# USB3-PCIEv21.net
KiCad netlist of a schematic drawn in Altium Designer
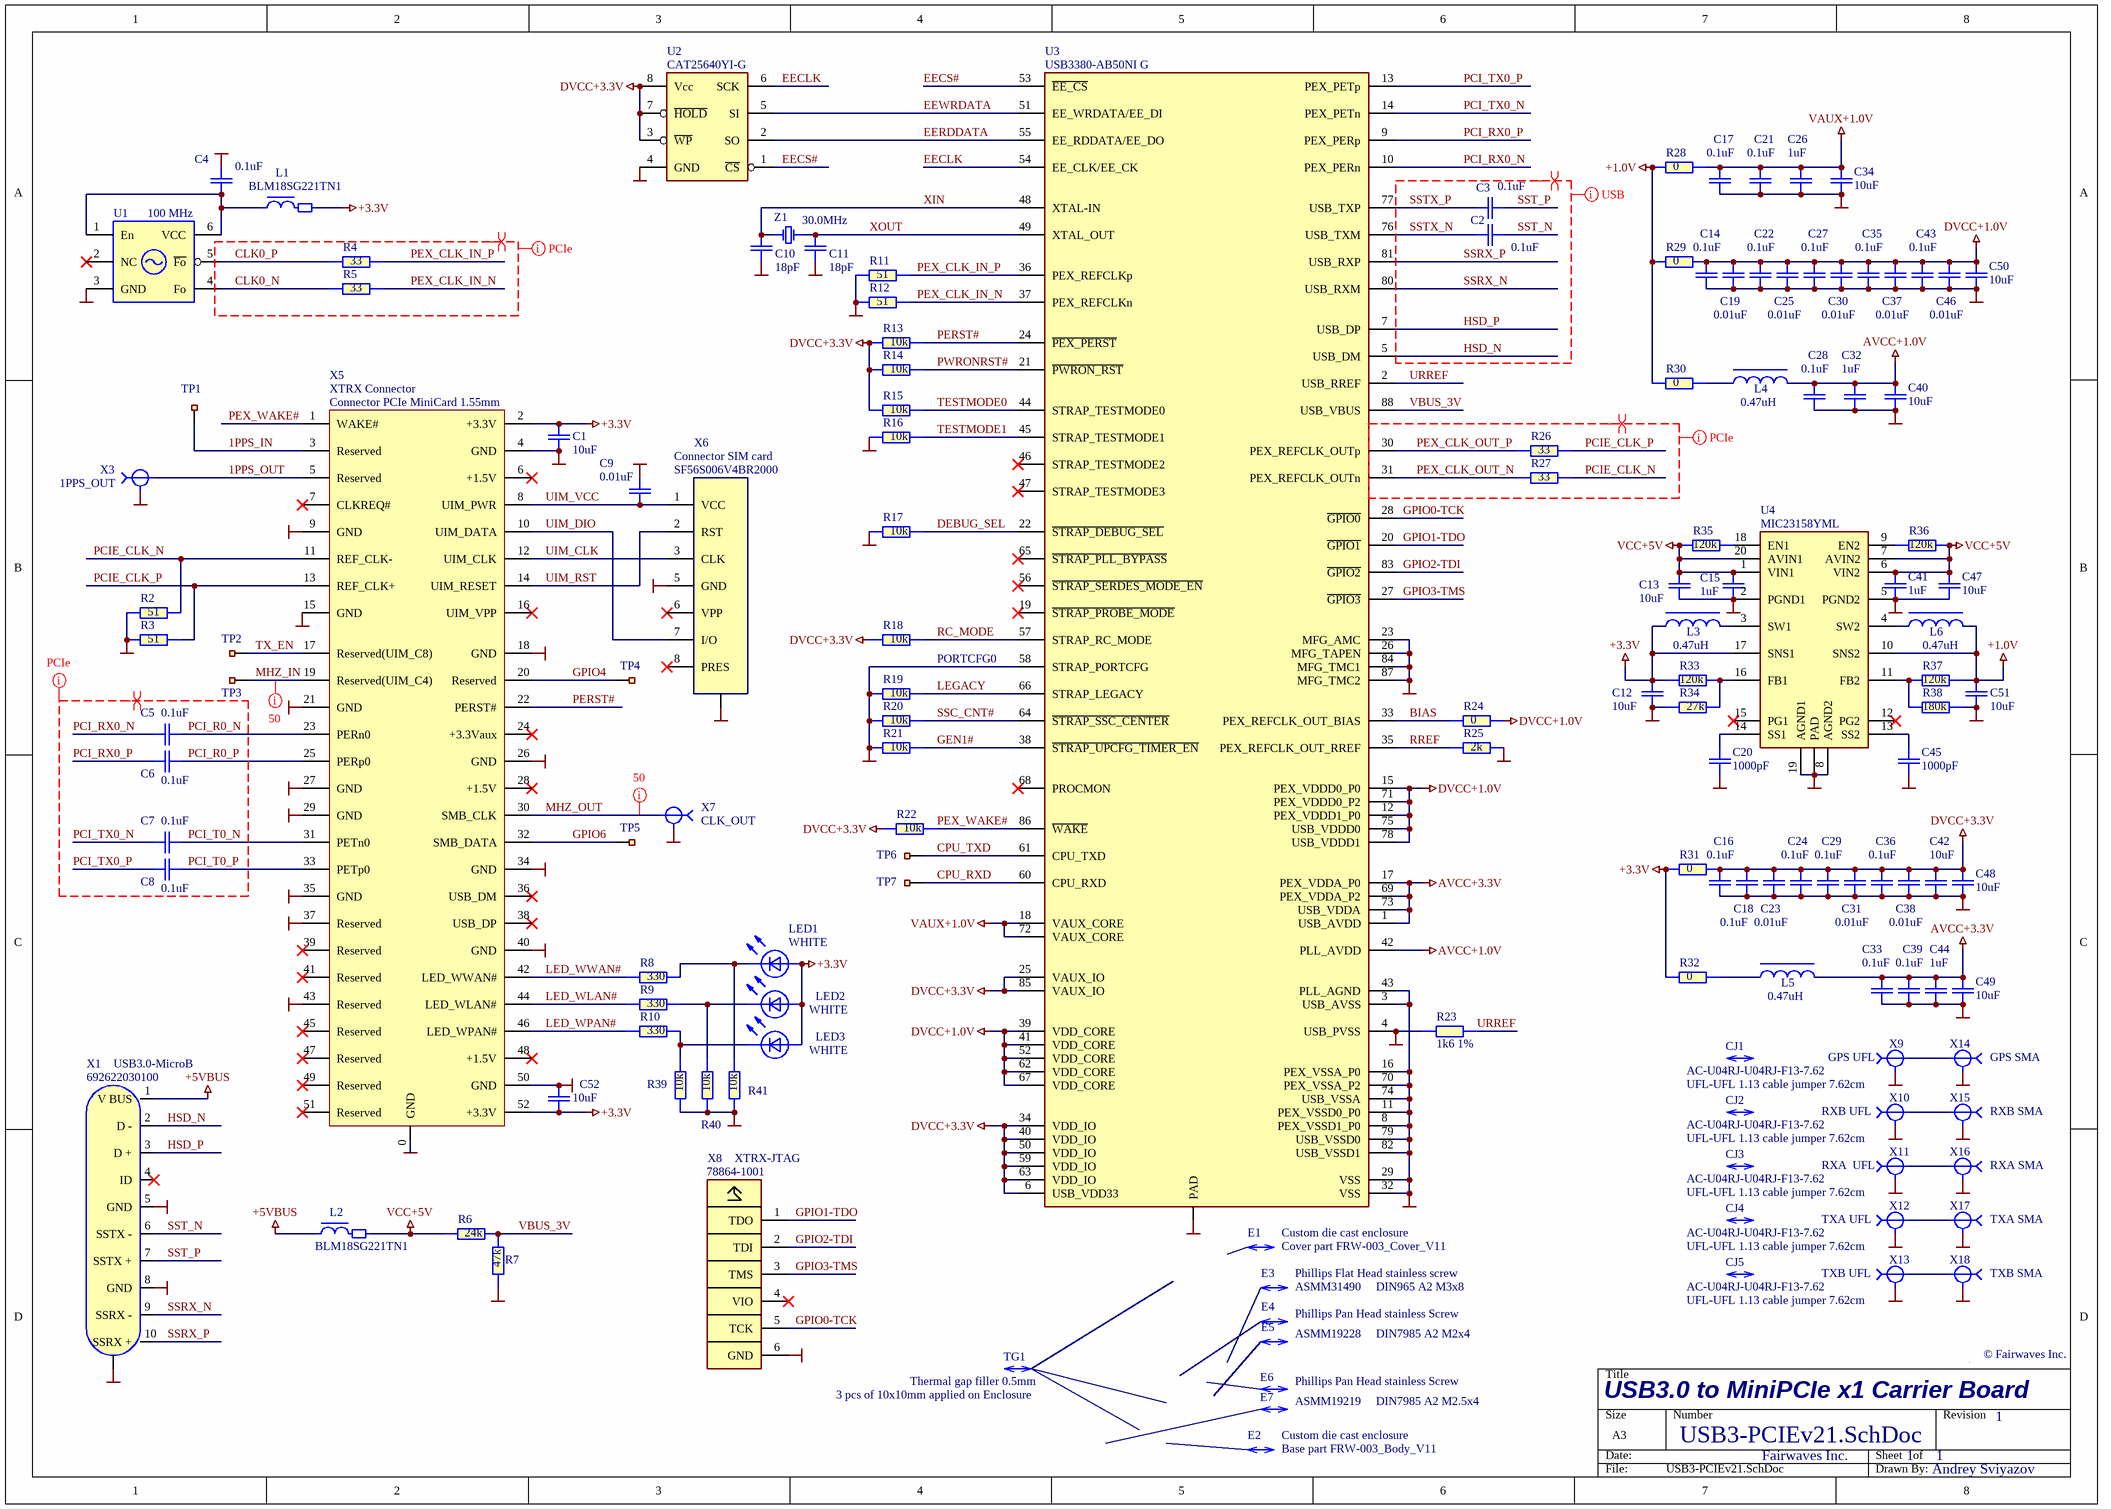
[diagram p0: USB3-PCIEv21.SchDoc]

(export (version "E")
  (design (tool "Eeschema 10.0.6"))
  (components
    (comp (ref "C1")
      (value "10uF")
      (footprint "C0402-Phillips")
      (description "Capacitor")
      (fields (field (name "MANUFACTURER") "MuRata") (field (name "TOLERANCE") "20%"))
      (libsource (lib "Capacitors") (part "C0402"))
    )
    (comp (ref "C2")
      (value "0.1uF")
      (footprint "C0402-Phillips")
      (description "Capacitor")
      (fields (field (name "MANUFACTURER") "YAGEO") (field (name "TOLERANCE") "20%"))
      (libsource (lib "Capacitors") (part "C0402"))
    )
    (comp (ref "C3")
      (value "0.1uF")
      (footprint "C0402-Phillips")
      (description "Capacitor")
      (fields (field (name "MANUFACTURER") "YAGEO") (field (name "TOLERANCE") "20%"))
      (libsource (lib "Capacitors") (part "C0402"))
    )
    (comp (ref "C4")
      (value "0.1uF")
      (footprint "C0402-Phillips")
      (description "Capacitor")
      (fields (field (name "MANUFACTURER") "YAGEO") (field (name "TOLERANCE") "20%"))
      (libsource (lib "Capacitors") (part "C0402"))
    )
    (comp (ref "C5")
      (value "0.1uF")
      (footprint "C0402-Phillips")
      (description "Capacitor")
      (fields (field (name "MANUFACTURER") "YAGEO") (field (name "TOLERANCE") "20%"))
      (libsource (lib "Capacitors") (part "C0402"))
    )
    (comp (ref "C6")
      (value "0.1uF")
      (footprint "C0402-Phillips")
      (description "Capacitor")
      (fields (field (name "MANUFACTURER") "YAGEO") (field (name "TOLERANCE") "20%"))
      (libsource (lib "Capacitors") (part "C0402"))
    )
    (comp (ref "C7")
      (value "0.1uF")
      (footprint "C0402-Phillips")
      (description "Capacitor")
      (fields (field (name "MANUFACTURER") "YAGEO") (field (name "TOLERANCE") "20%"))
      (libsource (lib "Capacitors") (part "C0402"))
    )
    (comp (ref "C8")
      (value "0.1uF")
      (footprint "C0402-Phillips")
      (description "Capacitor")
      (fields (field (name "MANUFACTURER") "YAGEO") (field (name "TOLERANCE") "20%"))
      (libsource (lib "Capacitors") (part "C0402"))
    )
    (comp (ref "C9")
      (value "0.01uF")
      (footprint "C0402-Phillips")
      (description "Capacitor")
      (fields (field (name "MANUFACTURER") "YAGEO") (field (name "TOLERANCE") "20%"))
      (libsource (lib "Capacitors") (part "C0402"))
    )
    (comp (ref "C10")
      (value "18pF")
      (footprint "C0402-Phillips")
      (description "Capacitor")
      (fields (field (name "MANUFACTURER") "Yageo") (field (name "TOLERANCE") "10%"))
      (libsource (lib "Capacitors") (part "C0402"))
    )
    (comp (ref "C11")
      (value "18pF")
      (footprint "C0402-Phillips")
      (description "Capacitor")
      (fields (field (name "MANUFACTURER") "Yageo") (field (name "TOLERANCE") "10%"))
      (libsource (lib "Capacitors") (part "C0402"))
    )
    (comp (ref "C12")
      (value "10uF")
      (footprint "C0402-Phillips")
      (description "Capacitor")
      (fields (field (name "MANUFACTURER") "MuRata") (field (name "TOLERANCE") "20%"))
      (libsource (lib "Capacitors") (part "C0402"))
    )
    (comp (ref "C13")
      (value "10uF")
      (footprint "C0402-Phillips")
      (description "Capacitor")
      (fields (field (name "MANUFACTURER") "MuRata") (field (name "TOLERANCE") "20%"))
      (libsource (lib "Capacitors") (part "C0402"))
    )
    (comp (ref "C14")
      (value "0.1uF")
      (footprint "C0402-Phillips")
      (description "Capacitor")
      (fields (field (name "MANUFACTURER") "YAGEO") (field (name "TOLERANCE") "20%"))
      (libsource (lib "Capacitors") (part "C0402"))
    )
    (comp (ref "C15")
      (value "1uF")
      (footprint "C0402-Phillips")
      (description "Capacitor")
      (fields (field (name "MANUFACTURER") "MuRata") (field (name "TOLERANCE") "20%"))
      (libsource (lib "Capacitors") (part "C0402"))
    )
    (comp (ref "C16")
      (value "0.1uF")
      (footprint "C0402-Phillips")
      (description "Capacitor")
      (fields (field (name "MANUFACTURER") "YAGEO") (field (name "TOLERANCE") "20%"))
      (libsource (lib "Capacitors") (part "C0402"))
    )
    (comp (ref "C17")
      (value "0.1uF")
      (footprint "C0402-Phillips")
      (description "Capacitor")
      (fields (field (name "MANUFACTURER") "YAGEO") (field (name "TOLERANCE") "20%"))
      (libsource (lib "Capacitors") (part "C0402"))
    )
    (comp (ref "C18")
      (value "0.1uF")
      (footprint "C0402-Phillips")
      (description "Capacitor")
      (fields (field (name "MANUFACTURER") "YAGEO") (field (name "TOLERANCE") "20%"))
      (libsource (lib "Capacitors") (part "C0402"))
    )
    (comp (ref "C19")
      (value "0.01uF")
      (footprint "C0402-Phillips")
      (description "Capacitor")
      (fields (field (name "MANUFACTURER") "YAGEO") (field (name "TOLERANCE") "20%"))
      (libsource (lib "Capacitors") (part "C0402"))
    )
    (comp (ref "C20")
      (value "1000pF")
      (footprint "C0402-Phillips")
      (description "Capacitor")
      (fields (field (name "MANUFACTURER") "MuRata") (field (name "TOLERANCE") "20%"))
      (libsource (lib "Capacitors") (part "C0402"))
    )
    (comp (ref "C21")
      (value "0.1uF")
      (footprint "C0402-Phillips")
      (description "Capacitor")
      (fields (field (name "MANUFACTURER") "YAGEO") (field (name "TOLERANCE") "20%"))
      (libsource (lib "Capacitors") (part "C0402"))
    )
    (comp (ref "C22")
      (value "0.1uF")
      (footprint "C0402-Phillips")
      (description "Capacitor")
      (fields (field (name "MANUFACTURER") "YAGEO") (field (name "TOLERANCE") "20%"))
      (libsource (lib "Capacitors") (part "C0402"))
    )
    (comp (ref "C23")
      (value "0.01uF")
      (footprint "C0402-Phillips")
      (description "Capacitor")
      (fields (field (name "MANUFACTURER") "YAGEO") (field (name "TOLERANCE") "20%"))
      (libsource (lib "Capacitors") (part "C0402"))
    )
    (comp (ref "C24")
      (value "0.1uF")
      (footprint "C0402-Phillips")
      (description "Capacitor")
      (fields (field (name "MANUFACTURER") "YAGEO") (field (name "TOLERANCE") "20%"))
      (libsource (lib "Capacitors") (part "C0402"))
    )
    (comp (ref "C25")
      (value "0.01uF")
      (footprint "C0402-Phillips")
      (description "Capacitor")
      (fields (field (name "MANUFACTURER") "YAGEO") (field (name "TOLERANCE") "20%"))
      (libsource (lib "Capacitors") (part "C0402"))
    )
    (comp (ref "C26")
      (value "1uF")
      (footprint "C0402-Phillips")
      (description "Capacitor")
      (fields (field (name "MANUFACTURER") "MuRata") (field (name "TOLERANCE") "20%"))
      (libsource (lib "Capacitors") (part "C0402"))
    )
    (comp (ref "C27")
      (value "0.1uF")
      (footprint "C0402-Phillips")
      (description "Capacitor")
      (fields (field (name "MANUFACTURER") "YAGEO") (field (name "TOLERANCE") "20%"))
      (libsource (lib "Capacitors") (part "C0402"))
    )
    (comp (ref "C28")
      (value "0.1uF")
      (footprint "C0402-Phillips")
      (description "Capacitor")
      (fields (field (name "MANUFACTURER") "YAGEO") (field (name "TOLERANCE") "20%"))
      (libsource (lib "Capacitors") (part "C0402"))
    )
    (comp (ref "C29")
      (value "0.1uF")
      (footprint "C0402-Phillips")
      (description "Capacitor")
      (fields (field (name "MANUFACTURER") "YAGEO") (field (name "TOLERANCE") "20%"))
      (libsource (lib "Capacitors") (part "C0402"))
    )
    (comp (ref "C30")
      (value "0.01uF")
      (footprint "C0402-Phillips")
      (description "Capacitor")
      (fields (field (name "MANUFACTURER") "YAGEO") (field (name "TOLERANCE") "20%"))
      (libsource (lib "Capacitors") (part "C0402"))
    )
    (comp (ref "C31")
      (value "0.01uF")
      (footprint "C0402-Phillips")
      (description "Capacitor")
      (fields (field (name "MANUFACTURER") "YAGEO") (field (name "TOLERANCE") "20%"))
      (libsource (lib "Capacitors") (part "C0402"))
    )
    (comp (ref "C32")
      (value "1uF")
      (footprint "C0402-Phillips")
      (description "Capacitor")
      (fields (field (name "MANUFACTURER") "MuRata") (field (name "TOLERANCE") "20%"))
      (libsource (lib "Capacitors") (part "C0402"))
    )
    (comp (ref "C33")
      (value "0.1uF")
      (footprint "C0402-Phillips")
      (description "Capacitor")
      (fields (field (name "MANUFACTURER") "YAGEO") (field (name "TOLERANCE") "20%"))
      (libsource (lib "Capacitors") (part "C0402"))
    )
    (comp (ref "C34")
      (value "10uF")
      (footprint "C0402-Phillips")
      (description "Capacitor")
      (fields (field (name "MANUFACTURER") "MuRata") (field (name "TOLERANCE") "20%"))
      (libsource (lib "Capacitors") (part "C0402"))
    )
    (comp (ref "C35")
      (value "0.1uF")
      (footprint "C0402-Phillips")
      (description "Capacitor")
      (fields (field (name "MANUFACTURER") "YAGEO") (field (name "TOLERANCE") "20%"))
      (libsource (lib "Capacitors") (part "C0402"))
    )
    (comp (ref "C36")
      (value "0.1uF")
      (footprint "C0402-Phillips")
      (description "Capacitor")
      (fields (field (name "MANUFACTURER") "YAGEO") (field (name "TOLERANCE") "20%"))
      (libsource (lib "Capacitors") (part "C0402"))
    )
    (comp (ref "C37")
      (value "0.01uF")
      (footprint "C0402-Phillips")
      (description "Capacitor")
      (fields (field (name "MANUFACTURER") "YAGEO") (field (name "TOLERANCE") "20%"))
      (libsource (lib "Capacitors") (part "C0402"))
    )
    (comp (ref "C38")
      (value "0.01uF")
      (footprint "C0402-Phillips")
      (description "Capacitor")
      (fields (field (name "MANUFACTURER") "YAGEO") (field (name "TOLERANCE") "20%"))
      (libsource (lib "Capacitors") (part "C0402"))
    )
    (comp (ref "C39")
      (value "0.1uF")
      (footprint "C0402-Phillips")
      (description "Capacitor")
      (fields (field (name "MANUFACTURER") "YAGEO") (field (name "TOLERANCE") "20%"))
      (libsource (lib "Capacitors") (part "C0402"))
    )
    (comp (ref "C40")
      (value "10uF")
      (footprint "C0402-Phillips")
      (description "Capacitor")
      (fields (field (name "MANUFACTURER") "MuRata") (field (name "TOLERANCE") "20%"))
      (libsource (lib "Capacitors") (part "C0402"))
    )
    (comp (ref "C41")
      (value "1uF")
      (footprint "C0402-Phillips")
      (description "Capacitor")
      (fields (field (name "MANUFACTURER") "MuRata") (field (name "TOLERANCE") "20%"))
      (libsource (lib "Capacitors") (part "C0402"))
    )
    (comp (ref "C42")
      (value "10uF")
      (footprint "C0402-Phillips")
      (description "Capacitor")
      (fields (field (name "MANUFACTURER") "MuRata") (field (name "TOLERANCE") "20%"))
      (libsource (lib "Capacitors") (part "C0402"))
    )
    (comp (ref "C43")
      (value "0.1uF")
      (footprint "C0402-Phillips")
      (description "Capacitor")
      (fields (field (name "MANUFACTURER") "YAGEO") (field (name "TOLERANCE") "20%"))
      (libsource (lib "Capacitors") (part "C0402"))
    )
    (comp (ref "C44")
      (value "1uF")
      (footprint "C0402-Phillips")
      (description "Capacitor")
      (fields (field (name "MANUFACTURER") "MuRata") (field (name "TOLERANCE") "20%"))
      (libsource (lib "Capacitors") (part "C0402"))
    )
    (comp (ref "C45")
      (value "1000pF")
      (footprint "C0402-Phillips")
      (description "Capacitor")
      (fields (field (name "MANUFACTURER") "MuRata") (field (name "TOLERANCE") "20%"))
      (libsource (lib "Capacitors") (part "C0402"))
    )
    (comp (ref "C46")
      (value "0.01uF")
      (footprint "C0402-Phillips")
      (description "Capacitor")
      (fields (field (name "MANUFACTURER") "YAGEO") (field (name "TOLERANCE") "20%"))
      (libsource (lib "Capacitors") (part "C0402"))
    )
    (comp (ref "C47")
      (value "10uF")
      (footprint "C0402-Phillips")
      (description "Capacitor")
      (fields (field (name "MANUFACTURER") "MuRata") (field (name "TOLERANCE") "20%"))
      (libsource (lib "Capacitors") (part "C0402"))
    )
    (comp (ref "C48")
      (value "10uF")
      (footprint "C0402-Phillips")
      (description "Capacitor")
      (fields (field (name "MANUFACTURER") "MuRata") (field (name "TOLERANCE") "20%"))
      (libsource (lib "Capacitors") (part "C0402"))
    )
    (comp (ref "C49")
      (value "10uF")
      (footprint "C0402-Phillips")
      (description "Capacitor")
      (fields (field (name "MANUFACTURER") "MuRata") (field (name "TOLERANCE") "20%"))
      (libsource (lib "Capacitors") (part "C0402"))
    )
    (comp (ref "C50")
      (value "10uF")
      (footprint "C0402-Phillips")
      (description "Capacitor")
      (fields (field (name "MANUFACTURER") "MuRata") (field (name "TOLERANCE") "20%"))
      (libsource (lib "Capacitors") (part "C0402"))
    )
    (comp (ref "C51")
      (value "10uF")
      (footprint "C0402-Phillips")
      (description "Capacitor")
      (fields (field (name "MANUFACTURER") "MuRata") (field (name "TOLERANCE") "20%"))
      (libsource (lib "Capacitors") (part "C0402"))
    )
    (comp (ref "C52")
      (value "10uF")
      (footprint "C0402-Phillips")
      (description "Capacitor")
      (fields (field (name "MANUFACTURER") "MuRata") (field (name "TOLERANCE") "20%"))
      (libsource (lib "Capacitors") (part "C0402"))
    )
    (comp (ref "CJ1")
      (value "AC-U04RJ-U04RJ-F13-7.62")
      (description "Cable jumper")
      (fields
        (field (name "MANUFACTURER") "RFSupplier")
        (field (name "MISC") "UFL-UFL 1.13 cable jumper 7.62cm")
      )
      (libsource (lib "Andy") (part "Mating part"))
    )
    (comp (ref "CJ2")
      (value "AC-U04RJ-U04RJ-F13-7.62")
      (description "Cable jumper")
      (fields
        (field (name "MANUFACTURER") "RFSupplier")
        (field (name "MISC") "UFL-UFL 1.13 cable jumper 7.62cm")
      )
      (libsource (lib "Andy") (part "Mating part"))
    )
    (comp (ref "CJ3")
      (value "AC-U04RJ-U04RJ-F13-7.62")
      (description "Cable jumper")
      (fields
        (field (name "MANUFACTURER") "RFSupplier")
        (field (name "MISC") "UFL-UFL 1.13 cable jumper 7.62cm")
      )
      (libsource (lib "Andy") (part "Mating part"))
    )
    (comp (ref "CJ4")
      (value "AC-U04RJ-U04RJ-F13-7.62")
      (description "Cable jumper")
      (fields
        (field (name "MANUFACTURER") "RFSupplier")
        (field (name "MISC") "UFL-UFL 1.13 cable jumper 7.62cm")
      )
      (libsource (lib "Andy") (part "Mating part"))
    )
    (comp (ref "CJ5")
      (value "AC-U04RJ-U04RJ-F13-7.62")
      (description "Cable jumper")
      (fields
        (field (name "MANUFACTURER") "RFSupplier")
        (field (name "MISC") "UFL-UFL 1.13 cable jumper 7.62cm")
      )
      (libsource (lib "Andy") (part "Mating part"))
    )
    (comp (ref "E1")
      (value "Cover part FRW-003_Cover_V11")
      (description "Custom die cast enclosure")
      (fields (field (name "MISC") "Custom die cast enclosure"))
      (libsource (lib "Andy") (part "Mating subpart 1"))
    )
    (comp (ref "E2")
      (value "Base part FRW-003_Body_V11")
      (description "Custom die cast enclosure")
      (fields (field (name "MISC") "Custom die cast enclosure"))
      (libsource (lib "Andy") (part "Mating subpart 1"))
    )
    (comp (ref "E3")
      (value "DIN965 A2 M3x8")
      (description "Screw M3")
      (fields
        (field (name "MANUFACTURER") "Aspen Fasteners")
        (field (name "MISC") "Phillips Flat Head stainless screw")
        (field (name "ALTIUM_VALUE") "ASMM31490")
      )
      (libsource (lib "Andy") (part "Mating subpart 1"))
    )
    (comp (ref "E4")
      (value "DIN7985 A2 M2x4")
      (description "Screw M2")
      (fields
        (field (name "MANUFACTURER") "Aspen Fasteners")
        (field (name "MISC") "Phillips Pan Head stainless Screw")
        (field (name "ALTIUM_VALUE") "ASMM19228")
      )
      (libsource (lib "Andy") (part "Mating subpart 1"))
    )
    (comp (ref "E5")
      (value "DIN7985 A2 M2x4")
      (description "Screw M2")
      (fields (field (name "MANUFACTURER") "Aspen Fasteners"))
      (libsource (lib "Andy") (part "Mating subpart 1"))
    )
    (comp (ref "E6")
      (value "DIN7985 A2 M2.5x4")
      (description "Screw M2.5")
      (fields
        (field (name "MANUFACTURER") "Aspen Fasteners")
        (field (name "MISC") "Phillips Pan Head stainless Screw")
        (field (name "ALTIUM_VALUE") "ASMM19219")
      )
      (libsource (lib "Andy") (part "Mating subpart 1"))
    )
    (comp (ref "E7")
      (value "DIN7985 A2 M2.5x4")
      (description "Screw M2.5")
      (fields (field (name "MANUFACTURER") "Aspen Fasteners"))
      (libsource (lib "Andy") (part "Mating subpart 1"))
    )
    (comp (ref "L1")
      (value "BLM18SG221TN1")
      (footprint "TI160808-Phillips")
      (description "EMI ferrite bead")
      (fields (field (name "MANUFACTURER") "MURATA"))
      (libsource (lib "Andy") (part "TI160808"))
    )
    (comp (ref "L2")
      (value "BLM18SG221TN1")
      (footprint "TI160808-Phillips")
      (description "EMI ferrite bead")
      (fields (field (name "MANUFACTURER") "MURATA"))
      (libsource (lib "Andy") (part "TI160808"))
    )
    (comp (ref "L3")
      (value "0.47uH")
      (footprint "L-VLS201610HBX")
      (description "Coil")
      (fields (field (name "MANUFACTURER") "TDK"))
      (libsource (lib "Andy") (part "L-VLS20161xHBX-1"))
    )
    (comp (ref "L4")
      (value "0.47uH")
      (footprint "L-VLS201610HBX")
      (description "Coil")
      (fields (field (name "MANUFACTURER") "TDK"))
      (libsource (lib "Andy") (part "L-VLS20161xHBX-1"))
    )
    (comp (ref "L5")
      (value "0.47uH")
      (footprint "L-VLS201610HBX")
      (description "Coil")
      (fields (field (name "MANUFACTURER") "TDK"))
      (libsource (lib "Andy") (part "L-VLS20161xHBX-1"))
    )
    (comp (ref "L6")
      (value "0.47uH")
      (footprint "L-VLS201610HBX")
      (description "Coil")
      (fields (field (name "MANUFACTURER") "TDK"))
      (libsource (lib "Andy") (part "L-VLS20161xHBX-1"))
    )
    (comp (ref "LED1")
      (value "WHITE")
      (footprint "Andy:LED-0603YL")
      (description "LED WHITE")
      (fields (field (name "MANUFACTURER") "Lite-On Inc"))
      (libsource (lib "Andy") (part "LED0603GR_Lite-On"))
    )
    (comp (ref "LED2")
      (value "WHITE")
      (footprint "Andy:LED-0603YL")
      (description "LED WHITE")
      (fields (field (name "MANUFACTURER") "Lite-On Inc"))
      (libsource (lib "Andy") (part "LED0603GR_Lite-On"))
    )
    (comp (ref "LED3")
      (value "WHITE")
      (footprint "Andy:LED-0603YL")
      (description "LED WHITE")
      (fields (field (name "MANUFACTURER") "Lite-On Inc"))
      (libsource (lib "Andy") (part "LED0603GR_Lite-On"))
    )
    (comp (ref "LOGO1")
      (value "© Fairwaves Inc.")
      (footprint "Andy:Logo Fairwaves")
      (libsource (lib "Andy") (part "Logo Fairwaves"))
    )
    (comp (ref "R2")
      (value "51")
      (footprint "R0402-Phillips")
      (description "Resistor")
      (fields (field (name "MANUFACTURER") "BOURNS") (field (name "TOLERANCE") "5%"))
      (libsource (lib "Andy") (part "R0402"))
    )
    (comp (ref "R3")
      (value "51")
      (footprint "R0402-Phillips")
      (description "Resistor")
      (fields (field (name "MANUFACTURER") "BOURNS") (field (name "TOLERANCE") "5%"))
      (libsource (lib "Andy") (part "R0402"))
    )
    (comp (ref "R4")
      (value "33")
      (footprint "R0402-Phillips")
      (description "Resistor")
      (fields (field (name "MANUFACTURER") "BOURNS") (field (name "TOLERANCE") "5%"))
      (libsource (lib "Andy") (part "R0402"))
    )
    (comp (ref "R5")
      (value "33")
      (footprint "R0402-Phillips")
      (description "Resistor")
      (fields (field (name "MANUFACTURER") "BOURNS") (field (name "TOLERANCE") "5%"))
      (libsource (lib "Andy") (part "R0402"))
    )
    (comp (ref "R6")
      (value "24k")
      (footprint "R0402-Phillips")
      (description "Resistor")
      (fields (field (name "MANUFACTURER") "BOURNS") (field (name "TOLERANCE") "5%"))
      (libsource (lib "Andy") (part "R0402"))
    )
    (comp (ref "R7")
      (value "47k")
      (footprint "R0402-Phillips")
      (description "Resistor")
      (fields (field (name "MANUFACTURER") "BOURNS") (field (name "TOLERANCE") "5%"))
      (libsource (lib "") (part "R0402_2"))
    )
    (comp (ref "R8")
      (value "330")
      (footprint "R0402-Phillips")
      (description "Resistor")
      (fields (field (name "MANUFACTURER") "BOURNS") (field (name "TOLERANCE") "5%"))
      (libsource (lib "Andy") (part "R0402"))
    )
    (comp (ref "R9")
      (value "330")
      (footprint "R0402-Phillips")
      (description "Resistor")
      (fields (field (name "MANUFACTURER") "BOURNS") (field (name "TOLERANCE") "5%"))
      (libsource (lib "Andy") (part "R0402"))
    )
    (comp (ref "R10")
      (value "330")
      (footprint "R0402-Phillips")
      (description "Resistor")
      (fields (field (name "MANUFACTURER") "BOURNS") (field (name "TOLERANCE") "5%"))
      (libsource (lib "Andy") (part "R0402"))
    )
    (comp (ref "R11")
      (value "51")
      (footprint "R0402-Phillips")
      (description "Resistor")
      (fields (field (name "MANUFACTURER") "BOURNS") (field (name "TOLERANCE") "5%"))
      (libsource (lib "Andy") (part "R0402"))
    )
    (comp (ref "R12")
      (value "51")
      (footprint "R0402-Phillips")
      (description "Resistor")
      (fields (field (name "MANUFACTURER") "BOURNS") (field (name "TOLERANCE") "5%"))
      (libsource (lib "Andy") (part "R0402"))
    )
    (comp (ref "R13")
      (value "10k")
      (footprint "R0402-Phillips")
      (description "Resistor")
      (fields (field (name "MANUFACTURER") "BOURNS") (field (name "TOLERANCE") "5%"))
      (libsource (lib "Andy") (part "R0402"))
    )
    (comp (ref "R14")
      (value "10k")
      (footprint "R0402-Phillips")
      (description "Resistor")
      (fields (field (name "MANUFACTURER") "BOURNS") (field (name "TOLERANCE") "5%"))
      (libsource (lib "Andy") (part "R0402"))
    )
    (comp (ref "R15")
      (value "10k")
      (footprint "R0402-Phillips")
      (description "Resistor")
      (fields (field (name "MANUFACTURER") "BOURNS") (field (name "TOLERANCE") "5%"))
      (libsource (lib "Andy") (part "R0402"))
    )
    (comp (ref "R16")
      (value "10k")
      (footprint "R0402-Phillips")
      (description "Resistor")
      (fields (field (name "MANUFACTURER") "BOURNS") (field (name "TOLERANCE") "5%"))
      (libsource (lib "Andy") (part "R0402"))
    )
    (comp (ref "R17")
      (value "10k")
      (footprint "R0402-Phillips")
      (description "Resistor")
      (fields (field (name "MANUFACTURER") "BOURNS") (field (name "TOLERANCE") "5%"))
      (libsource (lib "Andy") (part "R0402"))
    )
    (comp (ref "R18")
      (value "10k")
      (footprint "R0402-Phillips")
      (description "Resistor")
      (fields (field (name "MANUFACTURER") "BOURNS") (field (name "TOLERANCE") "5%"))
      (libsource (lib "Andy") (part "R0402"))
    )
    (comp (ref "R19")
      (value "10k")
      (footprint "R0402-Phillips")
      (description "Resistor")
      (fields (field (name "MANUFACTURER") "BOURNS") (field (name "TOLERANCE") "5%"))
      (libsource (lib "Andy") (part "R0402"))
    )
    (comp (ref "R20")
      (value "10k")
      (footprint "R0402-Phillips")
      (description "Resistor")
      (fields (field (name "MANUFACTURER") "BOURNS") (field (name "TOLERANCE") "5%"))
      (libsource (lib "Andy") (part "R0402"))
    )
    (comp (ref "R21")
      (value "10k")
      (footprint "R0402-Phillips")
      (description "Resistor")
      (fields (field (name "MANUFACTURER") "BOURNS") (field (name "TOLERANCE") "5%"))
      (libsource (lib "Andy") (part "R0402"))
    )
    (comp (ref "R22")
      (value "10k")
      (footprint "R0402-Phillips")
      (description "Resistor")
      (fields (field (name "MANUFACTURER") "BOURNS") (field (name "TOLERANCE") "5%"))
      (libsource (lib "Andy") (part "R0402"))
    )
    (comp (ref "R23")
      (value "1k6 1%")
      (footprint "R0402-Phillips")
      (description "Resistor")
      (fields (field (name "MANUFACTURER") "BOURNS") (field (name "TOLERANCE") "1%"))
      (libsource (lib "Andy") (part "R0402"))
    )
    (comp (ref "R24")
      (value "0")
      (footprint "R0402-Phillips")
      (description "Resistor")
      (fields (field (name "MANUFACTURER") "BOURNS") (field (name "TOLERANCE") "5%"))
      (libsource (lib "Andy") (part "R0402"))
    )
    (comp (ref "R25")
      (value "2k")
      (footprint "R0402-Phillips")
      (description "Resistor")
      (fields (field (name "MANUFACTURER") "BOURNS") (field (name "TOLERANCE") "5%"))
      (libsource (lib "Andy") (part "R0402"))
    )
    (comp (ref "R26")
      (value "33")
      (footprint "R0402-Phillips")
      (description "Resistor")
      (fields (field (name "MANUFACTURER") "BOURNS") (field (name "TOLERANCE") "5%"))
      (libsource (lib "Andy") (part "R0402"))
    )
    (comp (ref "R27")
      (value "33")
      (footprint "R0402-Phillips")
      (description "Resistor")
      (fields (field (name "MANUFACTURER") "BOURNS") (field (name "TOLERANCE") "5%"))
      (libsource (lib "Andy") (part "R0402"))
    )
    (comp (ref "R28")
      (value "0")
      (footprint "R0402-Phillips")
      (description "Resistor")
      (fields (field (name "MANUFACTURER") "BOURNS") (field (name "TOLERANCE") "5%"))
      (libsource (lib "Andy") (part "R0402"))
    )
    (comp (ref "R29")
      (value "0")
      (footprint "R0402-Phillips")
      (description "Resistor")
      (fields (field (name "MANUFACTURER") "BOURNS") (field (name "TOLERANCE") "5%"))
      (libsource (lib "Andy") (part "R0402"))
    )
    (comp (ref "R30")
      (value "0")
      (footprint "R0402-Phillips")
      (description "Resistor")
      (fields (field (name "MANUFACTURER") "BOURNS") (field (name "TOLERANCE") "5%"))
      (libsource (lib "Andy") (part "R0402"))
    )
    (comp (ref "R31")
      (value "0")
      (footprint "R0402-Phillips")
      (description "Resistor")
      (fields (field (name "MANUFACTURER") "BOURNS") (field (name "TOLERANCE") "5%"))
      (libsource (lib "Andy") (part "R0402"))
    )
    (comp (ref "R32")
      (value "0")
      (footprint "R0402-Phillips")
      (description "Resistor")
      (fields (field (name "MANUFACTURER") "BOURNS") (field (name "TOLERANCE") "5%"))
      (libsource (lib "Andy") (part "R0402"))
    )
    (comp (ref "R33")
      (value "120k")
      (footprint "R0402-Phillips")
      (description "Resistor")
      (fields (field (name "MANUFACTURER") "BOURNS") (field (name "TOLERANCE") "1%"))
      (libsource (lib "Andy") (part "R0402"))
    )
    (comp (ref "R34")
      (value "27k")
      (footprint "R0402-Phillips")
      (description "Resistor")
      (fields (field (name "MANUFACTURER") "BOURNS") (field (name "TOLERANCE") "1%"))
      (libsource (lib "Andy") (part "R0402"))
    )
    (comp (ref "R35")
      (value "120k")
      (footprint "R0402-Phillips")
      (description "Resistor")
      (fields (field (name "MANUFACTURER") "BOURNS") (field (name "TOLERANCE") "1%"))
      (libsource (lib "Andy") (part "R0402"))
    )
    (comp (ref "R36")
      (value "120k")
      (footprint "R0402-Phillips")
      (description "Resistor")
      (fields (field (name "MANUFACTURER") "BOURNS") (field (name "TOLERANCE") "1%"))
      (libsource (lib "Andy") (part "R0402"))
    )
    (comp (ref "R37")
      (value "120k")
      (footprint "R0402-Phillips")
      (description "Resistor")
      (fields (field (name "MANUFACTURER") "BOURNS") (field (name "TOLERANCE") "1%"))
      (libsource (lib "Andy") (part "R0402"))
    )
    (comp (ref "R38")
      (value "180k")
      (footprint "R0402-Phillips")
      (description "Resistor")
      (fields (field (name "MANUFACTURER") "BOURNS") (field (name "TOLERANCE") "1%"))
      (libsource (lib "Andy") (part "R0402"))
    )
    (comp (ref "R39")
      (value "10k")
      (footprint "R0402-Phillips")
      (description "Resistor")
      (fields (field (name "MANUFACTURER") "BOURNS") (field (name "TOLERANCE") "5%"))
      (libsource (lib "") (part "R0402_1"))
    )
    (comp (ref "R40")
      (value "10k")
      (footprint "R0402-Phillips")
      (description "Resistor")
      (fields (field (name "MANUFACTURER") "BOURNS") (field (name "TOLERANCE") "5%"))
      (libsource (lib "") (part "R0402_1"))
    )
    (comp (ref "R41")
      (value "10k")
      (footprint "R0402-Phillips")
      (description "Resistor")
      (fields (field (name "MANUFACTURER") "BOURNS") (field (name "TOLERANCE") "5%"))
      (libsource (lib "") (part "R0402_1"))
    )
    (comp (ref "TG1")
      (value "3 pcs of 10x10mm applied on Enclosure")
      (description "Thermal gap filler")
      (fields (field (name "MANUFACTURER") "Wakefield") (field (name "MISC") "Thermal gap filler 0.5mm"))
      (libsource (lib "Andy") (part "Mating subpart 1"))
    )
    (comp (ref "TP1")
      (value "~")
      (footprint "KP-C_d1mm")
      (description "Test point")
      (fields (field (name "MANUFACTURER") "PCB"))
      (libsource (lib "") (part "KP40X40_1"))
    )
    (comp (ref "TP2")
      (value "~")
      (footprint "KP-C_d1mm")
      (description "Test point")
      (fields (field (name "MANUFACTURER") "PCB"))
      (libsource (lib "Connectors") (part "KP40X40"))
    )
    (comp (ref "TP3")
      (value "~")
      (footprint "KP-C_d1mm")
      (description "Test point")
      (fields (field (name "MANUFACTURER") "PCB"))
      (libsource (lib "Connectors") (part "KP40X40"))
    )
    (comp (ref "TP4")
      (value "~")
      (footprint "KP-C_d1mm")
      (description "Test point")
      (fields (field (name "MANUFACTURER") "PCB"))
      (libsource (lib "") (part "KP40X40_2"))
    )
    (comp (ref "TP5")
      (value "~")
      (footprint "KP-C_d1mm")
      (description "Test point")
      (fields (field (name "MANUFACTURER") "PCB"))
      (libsource (lib "") (part "KP40X40_2"))
    )
    (comp (ref "TP6")
      (value "~")
      (footprint "KP-C_d1mm")
      (description "Test point")
      (fields (field (name "MANUFACTURER") "PCB"))
      (libsource (lib "Connectors") (part "KP40X40"))
    )
    (comp (ref "TP7")
      (value "~")
      (footprint "KP-C_d1mm")
      (description "Test point")
      (fields (field (name "MANUFACTURER") "PCB"))
      (libsource (lib "Connectors") (part "KP40X40"))
    )
    (comp (ref "U1")
      (value "100 MHz")
      (footprint "XO5X3.2-6pin")
      (description "Cristal Oscillator HSCL")
      (fields (field (name "MANUFACTURER") "Abracon LLC"))
      (libsource (lib "Andy") (part "XO_5x3.2_6pin"))
    )
    (comp (ref "U2")
      (value "CAT25640YI-G")
      (footprint "TSSOP-8")
      (description "IC SPI CMOS EEPROM")
      (fields (field (name "MANUFACTURER") "ON Semi"))
      (libsource (lib "Andy") (part "CAT25640"))
    )
    (comp (ref "U3")
      (value "USB3380-AB50NI G")
      (footprint "QFN-88(10x10/0.4mm)_pad")
      (description "IC")
      (fields (field (name "MANUFACTURER") "PLX Tech"))
      (libsource (lib "Andy") (part "USB3380"))
    )
    (comp (ref "U4")
      (value "MIC23158YML")
      (footprint "MLF-20(3X4/0.5)MIC")
      (description "IC dual 2A step down DCDC")
      (fields (field (name "MANUFACTURER") "MIcrochip"))
      (libsource (lib "Andy") (part "MIC23158_9"))
    )
    (comp (ref "X1")
      (value "692622030100")
      (footprint "Andy:USB3.0-MicroB SMT")
      (description "Connector microUSB3.0-Type B")
      (fields (field (name "MANUFACTURER") "Wurth") (field (name "NAME") "USB3.0-MicroB"))
      (libsource (lib "Andy") (part "USB3.0-MicroB"))
    )
    (comp (ref "X3")
      (value "0734120110")
      (footprint "U_FL")
      (description "Connector (UMCC)")
      (fields (field (name "MANUFACTURER") "Molex") (field (name "MISC") "1PPS_OUT"))
      (libsource (lib "Andy") (part "U_FL"))
    )
    (comp (ref "X5")
      (value "Connector PCIe MiniCard 1.55mm")
      (footprint "PCIe MiniCard 1.55mm conn")
      (fields (field (name "MANUFACTURER") "JAE Electronics") (field (name "ALTIUM_VALUE") "XTRX Connector"))
      (libsource (lib "Andy") (part "PCIe MiniCard conn h1.55mm"))
    )
    (comp (ref "X6")
      (value "Connector SIM card")
      (footprint "SIM_SF56S006V4BR2000-dig")
      (fields (field (name "NAME") "SF56S006V4BR2000") (field (name "MANUFACTURER") "JAE"))
      (libsource (lib "Andy") (part "SIM micro push-push"))
    )
    (comp (ref "X7")
      (value "0734120110")
      (footprint "U_FL")
      (description "Connector (UMCC)")
      (fields (field (name "MANUFACTURER") "Molex") (field (name "MISC") "CLK_OUT"))
      (libsource (lib "Andy") (part "U_FL"))
    )
    (comp (ref "X8")
      (value "XTRX-JTAG")
      (footprint "Molex 78864-1001")
      (description "Connector board to board")
      (fields (field (name "MANUFACTURER") "Molex") (field (name "NAME") "78864-1001"))
      (libsource (lib "Andy") (part "Conn Molex_788641001"))
    )
    (comp (ref "X9")
      (value "0734120110")
      (footprint "U_FL")
      (description "Connector (UMCC)")
      (fields (field (name "MANUFACTURER") "Molex") (field (name "MISC") "GPS UFL"))
      (libsource (lib "Andy") (part "U_FL"))
    )
    (comp (ref "X10")
      (value "0734120110")
      (footprint "U_FL")
      (description "Connector (UMCC)")
      (fields (field (name "MANUFACTURER") "Molex") (field (name "MISC") "RXB UFL"))
      (libsource (lib "Andy") (part "U_FL"))
    )
    (comp (ref "X11")
      (value "0734120110")
      (footprint "U_FL")
      (description "Connector (UMCC)")
      (fields (field (name "MANUFACTURER") "Molex") (field (name "MISC") "RXA  UFL"))
      (libsource (lib "Andy") (part "U_FL"))
    )
    (comp (ref "X12")
      (value "0734120110")
      (footprint "U_FL")
      (description "Connector (UMCC)")
      (fields (field (name "MANUFACTURER") "Molex") (field (name "MISC") "TXA UFL"))
      (libsource (lib "Andy") (part "U_FL"))
    )
    (comp (ref "X13")
      (value "0734120110")
      (footprint "U_FL")
      (description "Connector (UMCC)")
      (fields (field (name "MANUFACTURER") "Molex") (field (name "MISC") "TXB UFL"))
      (libsource (lib "Andy") (part "U_FL"))
    )
    (comp (ref "X14")
      (value "SMA edge SMD mount")
      (footprint "SMA - edge")
      (description "Connector coaxial")
      (fields (field (name "MANUFACTURER") "RFSupplier") (field (name "MISC") "GPS SMA"))
      (libsource (lib "Andy") (part "SMA EDGE SMD"))
    )
    (comp (ref "X15")
      (value "SMA edge SMD mount")
      (footprint "SMA - edge")
      (description "Connector coaxial")
      (fields (field (name "MANUFACTURER") "RFSupplier") (field (name "MISC") "RXB SMA"))
      (libsource (lib "Andy") (part "SMA EDGE SMD"))
    )
    (comp (ref "X16")
      (value "SMA edge SMD mount")
      (footprint "SMA - edge")
      (description "Connector coaxial")
      (fields (field (name "MANUFACTURER") "RFSupplier") (field (name "MISC") "RXA SMA"))
      (libsource (lib "Andy") (part "SMA EDGE SMD"))
    )
    (comp (ref "X17")
      (value "SMA edge SMD mount")
      (footprint "SMA - edge")
      (description "Connector coaxial")
      (fields (field (name "MANUFACTURER") "RFSupplier") (field (name "MISC") "TXA SMA"))
      (libsource (lib "Andy") (part "SMA EDGE SMD"))
    )
    (comp (ref "X18")
      (value "SMA edge SMD mount")
      (footprint "SMA - edge")
      (description "Connector coaxial")
      (fields (field (name "MANUFACTURER") "RFSupplier") (field (name "MISC") "TXB SMA"))
      (libsource (lib "Andy") (part "SMA EDGE SMD"))
    )
    (comp (ref "Z1")
      (value "30.0MHz")
      (footprint "ZQ_SMD2532")
      (description "Quartz crystall SMD")
      (fields (field (name "MANUFACTURER") "Abracon"))
      (libsource (lib "Andy") (part "ZQ2.5x3.2-SMD"))
    )
  )
  (nets
    (net (code "1") (name "+1.0V") (class "Default")
      (node (ref "C51") (pin "2") (pinfunction "2_2") (pintype "passive"))
      (node (ref "L6") (pin "2") (pinfunction "2_2") (pintype "passive"))
      (node (ref "R28") (pin "2") (pinfunction "2_2") (pintype "passive"))
      (node (ref "R29") (pin "2") (pinfunction "2_2") (pintype "passive"))
      (node (ref "R30") (pin "2") (pinfunction "2_2") (pintype "passive"))
      (node (ref "R37") (pin "1") (pinfunction "1_1") (pintype "passive"))
      (node (ref "U4") (pin "10") (pinfunction "SNS2_10") (pintype "passive"))
    )
    (net (code "2") (name "+3.3V") (class "Default")
      (node (ref "C1") (pin "2") (pinfunction "2_2") (pintype "passive"))
      (node (ref "C12") (pin "2") (pinfunction "2_2") (pintype "passive"))
      (node (ref "C52") (pin "1") (pinfunction "1_1") (pintype "passive"))
      (node (ref "L1") (pin "2") (pinfunction "2_2") (pintype "passive"))
      (node (ref "L3") (pin "1") (pinfunction "1_1") (pintype "passive"))
      (node (ref "LED1") (pin "2") (pinfunction "A_2") (pintype "passive"))
      (node (ref "LED2") (pin "2") (pinfunction "A_2") (pintype "passive"))
      (node (ref "LED3") (pin "2") (pinfunction "A_2") (pintype "passive"))
      (node (ref "R31") (pin "2") (pinfunction "2_2") (pintype "passive"))
      (node (ref "R32") (pin "2") (pinfunction "2_2") (pintype "passive"))
      (node (ref "R33") (pin "2") (pinfunction "2_2") (pintype "passive"))
      (node (ref "U4") (pin "17") (pinfunction "SNS1_17") (pintype "passive"))
      (node (ref "X5") (pin "2") (pinfunction "+3.3V_2") (pintype "passive"))
      (node (ref "X5") (pin "52") (pinfunction "+3.3V_52") (pintype "passive"))
    )
    (net (code "3") (name "+5VBUS") (class "Default")
      (node (ref "L2") (pin "1") (pinfunction "1_1") (pintype "passive"))
      (node (ref "X1") (pin "1") (pinfunction "V_BUS_1") (pintype "power_in"))
    )
    (net (code "4") (name "/1PPS_IN") (class "Default")
      (node (ref "TP1") (pin "1") (pinfunction "1_1") (pintype "passive"))
      (node (ref "X5") (pin "3") (pinfunction "Reserved_3") (pintype "passive"))
    )
    (net (code "5") (name "/1PPS_OUT") (class "Default")
      (node (ref "X3") (pin "1") (pinfunction "1_1") (pintype "passive"))
      (node (ref "X5") (pin "5") (pinfunction "Reserved_5") (pintype "passive"))
    )
    (net (code "6") (name "/BIAS") (class "Default")
      (node (ref "R24") (pin "2") (pinfunction "2_2") (pintype "passive"))
      (node (ref "U3") (pin "33") (pinfunction "PEX_REFCLK_OUT_BIAS_33") (pintype "passive"))
    )
    (net (code "7") (name "/CLK0_N") (class "Default")
      (node (ref "R5") (pin "2") (pinfunction "2_2") (pintype "passive"))
      (node (ref "U1") (pin "4") (pinfunction "Fo_4") (pintype "passive"))
    )
    (net (code "8") (name "/CLK0_P") (class "Default")
      (node (ref "R4") (pin "2") (pinfunction "2_2") (pintype "passive"))
      (node (ref "U1") (pin "5") (pinfunction "~{Fo}_5") (pintype "passive"))
    )
    (net (code "9") (name "/CPU_RXD") (class "Default")
      (node (ref "TP7") (pin "1") (pinfunction "1_1") (pintype "passive"))
      (node (ref "U3") (pin "60") (pinfunction "CPU_RXD_60") (pintype "passive"))
    )
    (net (code "10") (name "/CPU_TXD") (class "Default")
      (node (ref "TP6") (pin "1") (pinfunction "1_1") (pintype "passive"))
      (node (ref "U3") (pin "61") (pinfunction "CPU_TXD_61") (pintype "passive"))
    )
    (net (code "11") (name "/DEBUG_SEL") (class "Default")
      (node (ref "R17") (pin "1") (pinfunction "1_1") (pintype "passive"))
      (node (ref "U3") (pin "22") (pinfunction "~{STRAP_DEBUG_SEL}_22") (pintype "passive"))
    )
    (net (code "12") (name "/EECLK") (class "Default")
      (node (ref "U2") (pin "6") (pinfunction "SCK_6") (pintype "passive"))
      (node (ref "U3") (pin "54") (pinfunction "EE_CLK/EE_CK_54") (pintype "passive"))
    )
    (net (code "13") (name "/EECS#") (class "Default")
      (node (ref "U2") (pin "1") (pinfunction "~{CS}_1") (pintype "passive"))
      (node (ref "U3") (pin "53") (pinfunction "~{EE_CS}_53") (pintype "passive"))
    )
    (net (code "14") (name "/EERDDATA") (class "Default")
      (node (ref "U2") (pin "2") (pinfunction "SO_2") (pintype "passive"))
      (node (ref "U3") (pin "55") (pinfunction "EE_RDDATA/EE_DO_55") (pintype "passive"))
    )
    (net (code "15") (name "/EEWRDATA") (class "Default")
      (node (ref "U2") (pin "5") (pinfunction "SI_5") (pintype "passive"))
      (node (ref "U3") (pin "51") (pinfunction "EE_WRDATA/EE_DI_51") (pintype "passive"))
    )
    (net (code "16") (name "/GEN1#") (class "Default")
      (node (ref "R21") (pin "1") (pinfunction "1_1") (pintype "passive"))
      (node (ref "U3") (pin "38") (pinfunction "~{STRAP_UPCFG_TIMER_EN}_38") (pintype "passive"))
    )
    (net (code "17") (name "/GPIO0-TCK") (class "Default")
      (node (ref "U3") (pin "28") (pinfunction "~{GPIO0}_28") (pintype "passive"))
      (node (ref "X8") (pin "5") (pinfunction "TCK_5") (pintype "passive"))
    )
    (net (code "18") (name "/GPIO1-TDO") (class "Default")
      (node (ref "U3") (pin "20") (pinfunction "~{GPIO1}_20") (pintype "passive"))
      (node (ref "X8") (pin "1") (pinfunction "TDO_1") (pintype "passive"))
    )
    (net (code "19") (name "/GPIO2-TDI") (class "Default")
      (node (ref "U3") (pin "83") (pinfunction "~{GPIO2}_83") (pintype "passive"))
      (node (ref "X8") (pin "2") (pinfunction "TDI_2") (pintype "passive"))
    )
    (net (code "20") (name "/GPIO3-TMS") (class "Default")
      (node (ref "U3") (pin "27") (pinfunction "~{GPIO3}_27") (pintype "passive"))
      (node (ref "X8") (pin "3") (pinfunction "TMS_3") (pintype "passive"))
    )
    (net (code "21") (name "/GPIO4") (class "Default")
      (node (ref "TP4") (pin "1") (pinfunction "1_1") (pintype "passive"))
      (node (ref "X5") (pin "20") (pinfunction "Reserved_20") (pintype "passive"))
    )
    (net (code "22") (name "/GPIO6") (class "Default")
      (node (ref "TP5") (pin "1") (pinfunction "1_1") (pintype "passive"))
      (node (ref "X5") (pin "32") (pinfunction "SMB_DATA_32") (pintype "passive"))
    )
    (net (code "23") (name "/HSD_N") (class "Default")
      (node (ref "U3") (pin "5") (pinfunction "USB_DM_5") (pintype "passive"))
      (node (ref "X1") (pin "2") (pinfunction "D_-_2") (pintype "passive"))
    )
    (net (code "24") (name "/HSD_P") (class "Default")
      (node (ref "U3") (pin "7") (pinfunction "USB_DP_7") (pintype "passive"))
      (node (ref "X1") (pin "3") (pinfunction "D_+_3") (pintype "passive"))
    )
    (net (code "25") (name "/LED_WLAN#") (class "Default")
      (node (ref "R9") (pin "2") (pinfunction "2_2") (pintype "passive"))
      (node (ref "X5") (pin "44") (pinfunction "LED_WLAN#_44") (pintype "passive"))
    )
    (net (code "26") (name "/LED_WPAN#") (class "Default")
      (node (ref "R10") (pin "2") (pinfunction "2_2") (pintype "passive"))
      (node (ref "X5") (pin "46") (pinfunction "LED_WPAN#_46") (pintype "passive"))
    )
    (net (code "27") (name "/LED_WWAN#") (class "Default")
      (node (ref "R8") (pin "2") (pinfunction "2_2") (pintype "passive"))
      (node (ref "X5") (pin "42") (pinfunction "LED_WWAN#_42") (pintype "passive"))
    )
    (net (code "28") (name "/LEGACY") (class "Default")
      (node (ref "R19") (pin "1") (pinfunction "1_1") (pintype "passive"))
      (node (ref "U3") (pin "66") (pinfunction "STRAP_LEGACY_66") (pintype "passive"))
    )
    (net (code "29") (name "/MHZ_IN") (class "Default")
      (node (ref "TP3") (pin "1") (pinfunction "1_1") (pintype "passive"))
      (node (ref "X5") (pin "19") (pinfunction "Reserved(UIM_C4)_19") (pintype "passive"))
    )
    (net (code "30") (name "/MHZ_OUT") (class "Default")
      (node (ref "X5") (pin "30") (pinfunction "SMB_CLK_30") (pintype "passive"))
      (node (ref "X7") (pin "1") (pinfunction "1_1") (pintype "passive"))
    )
    (net (code "31") (name "/PCIE_CLK_N") (class "Default")
      (node (ref "R2") (pin "1") (pinfunction "1_1") (pintype "passive"))
      (node (ref "R27") (pin "1") (pinfunction "1_1") (pintype "passive"))
      (node (ref "X5") (pin "11") (pinfunction "REF_CLK-_11") (pintype "passive"))
    )
    (net (code "32") (name "/PCIE_CLK_P") (class "Default")
      (node (ref "R26") (pin "1") (pinfunction "1_1") (pintype "passive"))
      (node (ref "R3") (pin "1") (pinfunction "1_1") (pintype "passive"))
      (node (ref "X5") (pin "13") (pinfunction "REF_CLK+_13") (pintype "passive"))
    )
    (net (code "33") (name "/PCI_R0_N") (class "Default")
      (node (ref "C5") (pin "1") (pinfunction "1_1") (pintype "passive"))
      (node (ref "X5") (pin "23") (pinfunction "PERn0_23") (pintype "passive"))
    )
    (net (code "34") (name "/PCI_R0_P") (class "Default")
      (node (ref "C6") (pin "1") (pinfunction "1_1") (pintype "passive"))
      (node (ref "X5") (pin "25") (pinfunction "PERp0_25") (pintype "passive"))
    )
    (net (code "35") (name "/PCI_RX0_N") (class "Default")
      (node (ref "C5") (pin "2") (pinfunction "2_2") (pintype "passive"))
      (node (ref "U3") (pin "10") (pinfunction "PEX_PERn_10") (pintype "passive"))
    )
    (net (code "36") (name "/PCI_RX0_P") (class "Default")
      (node (ref "C6") (pin "2") (pinfunction "2_2") (pintype "passive"))
      (node (ref "U3") (pin "9") (pinfunction "PEX_PERp_9") (pintype "passive"))
    )
    (net (code "37") (name "/PCI_T0_N") (class "Default")
      (node (ref "C7") (pin "1") (pinfunction "1_1") (pintype "passive"))
      (node (ref "X5") (pin "31") (pinfunction "PETn0_31") (pintype "passive"))
    )
    (net (code "38") (name "/PCI_T0_P") (class "Default")
      (node (ref "C8") (pin "1") (pinfunction "1_1") (pintype "passive"))
      (node (ref "X5") (pin "33") (pinfunction "PETp0_33") (pintype "passive"))
    )
    (net (code "39") (name "/PCI_TX0_N") (class "Default")
      (node (ref "C7") (pin "2") (pinfunction "2_2") (pintype "passive"))
      (node (ref "U3") (pin "14") (pinfunction "PEX_PETn_14") (pintype "passive"))
    )
    (net (code "40") (name "/PCI_TX0_P") (class "Default")
      (node (ref "C8") (pin "2") (pinfunction "2_2") (pintype "passive"))
      (node (ref "U3") (pin "13") (pinfunction "PEX_PETp_13") (pintype "passive"))
    )
    (net (code "41") (name "/PERST#") (class "Default")
      (node (ref "R13") (pin "1") (pinfunction "1_1") (pintype "passive"))
      (node (ref "U3") (pin "24") (pinfunction "~{PEX_PERST}_24") (pintype "passive"))
      (node (ref "X5") (pin "22") (pinfunction "PERST#_22") (pintype "passive"))
    )
    (net (code "42") (name "/PEX_CLK_IN_N") (class "Default")
      (node (ref "R12") (pin "1") (pinfunction "1_1") (pintype "passive"))
      (node (ref "R5") (pin "1") (pinfunction "1_1") (pintype "passive"))
      (node (ref "U3") (pin "37") (pinfunction "PEX_REFCLKn_37") (pintype "passive"))
    )
    (net (code "43") (name "/PEX_CLK_IN_P") (class "Default")
      (node (ref "R11") (pin "1") (pinfunction "1_1") (pintype "passive"))
      (node (ref "R4") (pin "1") (pinfunction "1_1") (pintype "passive"))
      (node (ref "U3") (pin "36") (pinfunction "PEX_REFCLKp_36") (pintype "passive"))
    )
    (net (code "44") (name "/PEX_CLK_OUT_N") (class "Default")
      (node (ref "R27") (pin "2") (pinfunction "2_2") (pintype "passive"))
      (node (ref "U3") (pin "31") (pinfunction "PEX_REFCLK_OUTn_31") (pintype "passive"))
    )
    (net (code "45") (name "/PEX_CLK_OUT_P") (class "Default")
      (node (ref "R26") (pin "2") (pinfunction "2_2") (pintype "passive"))
      (node (ref "U3") (pin "30") (pinfunction "PEX_REFCLK_OUTp_30") (pintype "passive"))
    )
    (net (code "46") (name "/PEX_WAKE#") (class "Default")
      (node (ref "R22") (pin "1") (pinfunction "1_1") (pintype "passive"))
      (node (ref "U3") (pin "86") (pinfunction "~{WAKE}_86") (pintype "passive"))
      (node (ref "X5") (pin "1") (pinfunction "WAKE#_1") (pintype "passive"))
    )
    (net (code "47") (name "/PWRONRST#") (class "Default")
      (node (ref "R14") (pin "1") (pinfunction "1_1") (pintype "passive"))
      (node (ref "U3") (pin "21") (pinfunction "~{PWRON_RST}_21") (pintype "passive"))
    )
    (net (code "48") (name "/RC_MODE") (class "Default")
      (node (ref "R18") (pin "1") (pinfunction "1_1") (pintype "passive"))
      (node (ref "U3") (pin "57") (pinfunction "STRAP_RC_MODE_57") (pintype "passive"))
    )
    (net (code "49") (name "/RREF") (class "Default")
      (node (ref "R25") (pin "2") (pinfunction "2_2") (pintype "passive"))
      (node (ref "U3") (pin "35") (pinfunction "PEX_REFCLK_OUT_RREF_35") (pintype "passive"))
    )
    (net (code "50") (name "/SSC_CNT#") (class "Default")
      (node (ref "R20") (pin "1") (pinfunction "1_1") (pintype "passive"))
      (node (ref "U3") (pin "64") (pinfunction "~{STRAP_SSC_CENTER}_64") (pintype "passive"))
    )
    (net (code "51") (name "/SSRX_N") (class "Default")
      (node (ref "U3") (pin "80") (pinfunction "USB_RXM_80") (pintype "passive"))
      (node (ref "X1") (pin "9") (pinfunction "SSRX_-_9") (pintype "passive"))
    )
    (net (code "52") (name "/SSRX_P") (class "Default")
      (node (ref "U3") (pin "81") (pinfunction "USB_RXP_81") (pintype "passive"))
      (node (ref "X1") (pin "10") (pinfunction "SSRX_+_10") (pintype "passive"))
    )
    (net (code "53") (name "/SSTX_N") (class "Default")
      (node (ref "C2") (pin "1") (pinfunction "1_1") (pintype "passive"))
      (node (ref "U3") (pin "76") (pinfunction "USB_TXM_76") (pintype "passive"))
    )
    (net (code "54") (name "/SSTX_P") (class "Default")
      (node (ref "C3") (pin "1") (pinfunction "1_1") (pintype "passive"))
      (node (ref "U3") (pin "77") (pinfunction "USB_TXP_77") (pintype "passive"))
    )
    (net (code "55") (name "/SST_N") (class "Default")
      (node (ref "C2") (pin "2") (pinfunction "2_2") (pintype "passive"))
      (node (ref "X1") (pin "6") (pinfunction "SSTX_-_6") (pintype "passive"))
    )
    (net (code "56") (name "/SST_P") (class "Default")
      (node (ref "C3") (pin "2") (pinfunction "2_2") (pintype "passive"))
      (node (ref "X1") (pin "7") (pinfunction "SSTX_+_7") (pintype "passive"))
    )
    (net (code "57") (name "/TESTMODE0") (class "Default")
      (node (ref "R15") (pin "1") (pinfunction "1_1") (pintype "passive"))
      (node (ref "U3") (pin "44") (pinfunction "STRAP_TESTMODE0_44") (pintype "passive"))
    )
    (net (code "58") (name "/TESTMODE1") (class "Default")
      (node (ref "R16") (pin "1") (pinfunction "1_1") (pintype "passive"))
      (node (ref "U3") (pin "45") (pinfunction "STRAP_TESTMODE1_45") (pintype "passive"))
    )
    (net (code "59") (name "/TX_EN") (class "Default")
      (node (ref "TP2") (pin "1") (pinfunction "1_1") (pintype "passive"))
      (node (ref "X5") (pin "17") (pinfunction "Reserved(UIM_C8)_17") (pintype "passive"))
    )
    (net (code "60") (name "/UIM_CLK") (class "Default")
      (node (ref "X5") (pin "12") (pinfunction "UIM_CLK_12") (pintype "passive"))
      (node (ref "X6") (pin "3") (pinfunction "CLK_3") (pintype "passive"))
    )
    (net (code "61") (name "/UIM_DIO") (class "Default")
      (node (ref "X5") (pin "10") (pinfunction "UIM_DATA_10") (pintype "passive"))
      (node (ref "X6") (pin "7") (pinfunction "I/O_7") (pintype "passive"))
    )
    (net (code "62") (name "/UIM_RST") (class "Default")
      (node (ref "X5") (pin "14") (pinfunction "UIM_RESET_14") (pintype "passive"))
      (node (ref "X6") (pin "2") (pinfunction "RST_2") (pintype "passive"))
    )
    (net (code "63") (name "/UIM_VCC") (class "Default")
      (node (ref "C9") (pin "1") (pinfunction "1_1") (pintype "passive"))
      (node (ref "X5") (pin "8") (pinfunction "UIM_PWR_8") (pintype "passive"))
      (node (ref "X6") (pin "1") (pinfunction "VCC_1") (pintype "passive"))
    )
    (net (code "64") (name "/URREF") (class "Default")
      (node (ref "R23") (pin "1") (pinfunction "1_1") (pintype "passive"))
      (node (ref "U3") (pin "2") (pinfunction "USB_RREF_2") (pintype "passive"))
    )
    (net (code "65") (name "/VBUS_3V") (class "Default")
      (node (ref "R6") (pin "1") (pinfunction "1_1") (pintype "passive"))
      (node (ref "R7") (pin "2") (pinfunction "2_2") (pintype "passive"))
      (node (ref "U3") (pin "88") (pinfunction "USB_VBUS_88") (pintype "passive"))
    )
    (net (code "66") (name "/XIN") (class "Default")
      (node (ref "C10") (pin "2") (pinfunction "2_2") (pintype "passive"))
      (node (ref "U3") (pin "48") (pinfunction "XTAL-IN_48") (pintype "passive"))
      (node (ref "Z1") (pin "1") (pinfunction "1_1") (pintype "passive"))
    )
    (net (code "67") (name "/XOUT") (class "Default")
      (node (ref "C11") (pin "2") (pinfunction "2_2") (pintype "passive"))
      (node (ref "U3") (pin "49") (pinfunction "XTAL_OUT_49") (pintype "passive"))
      (node (ref "Z1") (pin "3") (pinfunction "3_3") (pintype "passive"))
    )
    (net (code "68") (name "AVCC+1.0V") (class "Default")
      (node (ref "C28") (pin "1") (pinfunction "1_1") (pintype "passive"))
      (node (ref "C32") (pin "2") (pinfunction "2_2") (pintype "passive"))
      (node (ref "C40") (pin "2") (pinfunction "2_2") (pintype "passive"))
      (node (ref "L4") (pin "2") (pinfunction "2_2") (pintype "passive"))
      (node (ref "U3") (pin "42") (pinfunction "PLL_AVDD_42") (pintype "passive"))
    )
    (net (code "69") (name "AVCC+3.3V") (class "Default")
      (node (ref "C33") (pin "1") (pinfunction "1_1") (pintype "passive"))
      (node (ref "C39") (pin "1") (pinfunction "1_1") (pintype "passive"))
      (node (ref "C44") (pin "2") (pinfunction "2_2") (pintype "passive"))
      (node (ref "C49") (pin "2") (pinfunction "2_2") (pintype "passive"))
      (node (ref "L5") (pin "2") (pinfunction "2_2") (pintype "passive"))
      (node (ref "U3") (pin "1") (pinfunction "USB_AVDD_1") (pintype "passive"))
      (node (ref "U3") (pin "17") (pinfunction "PEX_VDDA_P0_17") (pintype "passive"))
      (node (ref "U3") (pin "69") (pinfunction "PEX_VDDA_P2_69") (pintype "passive"))
      (node (ref "U3") (pin "73") (pinfunction "USB_VDDA_73") (pintype "passive"))
    )
    (net (code "70") (name "DVCC+1.0V") (class "Default")
      (node (ref "C14") (pin "1") (pinfunction "1_1") (pintype "passive"))
      (node (ref "C19") (pin "2") (pinfunction "2_2") (pintype "passive"))
      (node (ref "C22") (pin "1") (pinfunction "1_1") (pintype "passive"))
      (node (ref "C25") (pin "2") (pinfunction "2_2") (pintype "passive"))
      (node (ref "C27") (pin "1") (pinfunction "1_1") (pintype "passive"))
      (node (ref "C30") (pin "2") (pinfunction "2_2") (pintype "passive"))
      (node (ref "C35") (pin "1") (pinfunction "1_1") (pintype "passive"))
      (node (ref "C37") (pin "2") (pinfunction "2_2") (pintype "passive"))
      (node (ref "C43") (pin "1") (pinfunction "1_1") (pintype "passive"))
      (node (ref "C46") (pin "2") (pinfunction "2_2") (pintype "passive"))
      (node (ref "C50") (pin "2") (pinfunction "2_2") (pintype "passive"))
      (node (ref "R24") (pin "1") (pinfunction "1_1") (pintype "passive"))
      (node (ref "R29") (pin "1") (pinfunction "1_1") (pintype "passive"))
      (node (ref "U3") (pin "12") (pinfunction "PEX_VDDD1_P0_12") (pintype "passive"))
      (node (ref "U3") (pin "15") (pinfunction "PEX_VDDD0_P0_15") (pintype "passive"))
      (node (ref "U3") (pin "39") (pinfunction "VDD_CORE_39") (pintype "passive"))
      (node (ref "U3") (pin "41") (pinfunction "VDD_CORE_41") (pintype "passive"))
      (node (ref "U3") (pin "52") (pinfunction "VDD_CORE_52") (pintype "passive"))
      (node (ref "U3") (pin "62") (pinfunction "VDD_CORE_62") (pintype "passive"))
      (node (ref "U3") (pin "67") (pinfunction "VDD_CORE_67") (pintype "passive"))
      (node (ref "U3") (pin "71") (pinfunction "PEX_VDDD0_P2_71") (pintype "passive"))
      (node (ref "U3") (pin "75") (pinfunction "USB_VDDD0_75") (pintype "passive"))
      (node (ref "U3") (pin "78") (pinfunction "USB_VDDD1_78") (pintype "passive"))
    )
    (net (code "71") (name "DVCC+3.3V") (class "Default")
      (node (ref "C16") (pin "1") (pinfunction "1_1") (pintype "passive"))
      (node (ref "C18") (pin "1") (pinfunction "1_1") (pintype "passive"))
      (node (ref "C23") (pin "2") (pinfunction "2_2") (pintype "passive"))
      (node (ref "C24") (pin "1") (pinfunction "1_1") (pintype "passive"))
      (node (ref "C29") (pin "1") (pinfunction "1_1") (pintype "passive"))
      (node (ref "C31") (pin "2") (pinfunction "2_2") (pintype "passive"))
      (node (ref "C36") (pin "1") (pinfunction "1_1") (pintype "passive"))
      (node (ref "C38") (pin "2") (pinfunction "2_2") (pintype "passive"))
      (node (ref "C42") (pin "2") (pinfunction "2_2") (pintype "passive"))
      (node (ref "C48") (pin "2") (pinfunction "2_2") (pintype "passive"))
      (node (ref "R13") (pin "2") (pinfunction "2_2") (pintype "passive"))
      (node (ref "R14") (pin "2") (pinfunction "2_2") (pintype "passive"))
      (node (ref "R15") (pin "2") (pinfunction "2_2") (pintype "passive"))
      (node (ref "R18") (pin "2") (pinfunction "2_2") (pintype "passive"))
      (node (ref "R22") (pin "2") (pinfunction "2_2") (pintype "passive"))
      (node (ref "R31") (pin "1") (pinfunction "1_1") (pintype "passive"))
      (node (ref "U2") (pin "3") (pinfunction "~{WP}_3") (pintype "passive"))
      (node (ref "U2") (pin "7") (pinfunction "~{HOLD}_7") (pintype "passive"))
      (node (ref "U2") (pin "8") (pinfunction "Vcc_8") (pintype "passive"))
      (node (ref "U3") (pin "25") (pinfunction "VAUX_IO_25") (pintype "passive"))
      (node (ref "U3") (pin "34") (pinfunction "VDD_IO_34") (pintype "passive"))
      (node (ref "U3") (pin "40") (pinfunction "VDD_IO_40") (pintype "passive"))
      (node (ref "U3") (pin "50") (pinfunction "VDD_IO_50") (pintype "passive"))
      (node (ref "U3") (pin "59") (pinfunction "VDD_IO_59") (pintype "passive"))
      (node (ref "U3") (pin "6") (pinfunction "USB_VDD33_6") (pintype "passive"))
      (node (ref "U3") (pin "63") (pinfunction "VDD_IO_63") (pintype "passive"))
      (node (ref "U3") (pin "85") (pinfunction "VAUX_IO_85") (pintype "passive"))
    )
    (net (code "72") (name "GND") (class "Default")
      (node (ref "C1") (pin "1") (pinfunction "1_1") (pintype "passive"))
      (node (ref "C10") (pin "1") (pinfunction "1_1") (pintype "passive"))
      (node (ref "C11") (pin "1") (pinfunction "1_1") (pintype "passive"))
      (node (ref "C12") (pin "1") (pinfunction "1_1") (pintype "passive"))
      (node (ref "C13") (pin "1") (pinfunction "1_1") (pintype "passive"))
      (node (ref "C14") (pin "2") (pinfunction "2_2") (pintype "passive"))
      (node (ref "C15") (pin "1") (pinfunction "1_1") (pintype "passive"))
      (node (ref "C16") (pin "2") (pinfunction "2_2") (pintype "passive"))
      (node (ref "C17") (pin "2") (pinfunction "2_2") (pintype "passive"))
      (node (ref "C18") (pin "2") (pinfunction "2_2") (pintype "passive"))
      (node (ref "C19") (pin "1") (pinfunction "1_1") (pintype "passive"))
      (node (ref "C20") (pin "1") (pinfunction "1_1") (pintype "passive"))
      (node (ref "C21") (pin "2") (pinfunction "2_2") (pintype "passive"))
      (node (ref "C22") (pin "2") (pinfunction "2_2") (pintype "passive"))
      (node (ref "C23") (pin "1") (pinfunction "1_1") (pintype "passive"))
      (node (ref "C24") (pin "2") (pinfunction "2_2") (pintype "passive"))
      (node (ref "C25") (pin "1") (pinfunction "1_1") (pintype "passive"))
      (node (ref "C26") (pin "1") (pinfunction "1_1") (pintype "passive"))
      (node (ref "C27") (pin "2") (pinfunction "2_2") (pintype "passive"))
      (node (ref "C28") (pin "2") (pinfunction "2_2") (pintype "passive"))
      (node (ref "C29") (pin "2") (pinfunction "2_2") (pintype "passive"))
      (node (ref "C30") (pin "1") (pinfunction "1_1") (pintype "passive"))
      (node (ref "C31") (pin "1") (pinfunction "1_1") (pintype "passive"))
      (node (ref "C32") (pin "1") (pinfunction "1_1") (pintype "passive"))
      (node (ref "C33") (pin "2") (pinfunction "2_2") (pintype "passive"))
      (node (ref "C34") (pin "1") (pinfunction "1_1") (pintype "passive"))
      (node (ref "C35") (pin "2") (pinfunction "2_2") (pintype "passive"))
      (node (ref "C36") (pin "2") (pinfunction "2_2") (pintype "passive"))
      (node (ref "C37") (pin "1") (pinfunction "1_1") (pintype "passive"))
      (node (ref "C38") (pin "1") (pinfunction "1_1") (pintype "passive"))
      (node (ref "C39") (pin "2") (pinfunction "2_2") (pintype "passive"))
      (node (ref "C4") (pin "1") (pinfunction "1_1") (pintype "passive"))
      (node (ref "C40") (pin "1") (pinfunction "1_1") (pintype "passive"))
      (node (ref "C41") (pin "1") (pinfunction "1_1") (pintype "passive"))
      (node (ref "C42") (pin "1") (pinfunction "1_1") (pintype "passive"))
      (node (ref "C43") (pin "2") (pinfunction "2_2") (pintype "passive"))
      (node (ref "C44") (pin "1") (pinfunction "1_1") (pintype "passive"))
      (node (ref "C45") (pin "1") (pinfunction "1_1") (pintype "passive"))
      (node (ref "C46") (pin "1") (pinfunction "1_1") (pintype "passive"))
      (node (ref "C47") (pin "1") (pinfunction "1_1") (pintype "passive"))
      (node (ref "C48") (pin "1") (pinfunction "1_1") (pintype "passive"))
      (node (ref "C49") (pin "1") (pinfunction "1_1") (pintype "passive"))
      (node (ref "C50") (pin "1") (pinfunction "1_1") (pintype "passive"))
      (node (ref "C51") (pin "1") (pinfunction "1_1") (pintype "passive"))
      (node (ref "C52") (pin "2") (pinfunction "2_2") (pintype "passive"))
      (node (ref "C9") (pin "2") (pinfunction "2_2") (pintype "passive"))
      (node (ref "R11") (pin "2") (pinfunction "2_2") (pintype "passive"))
      (node (ref "R12") (pin "2") (pinfunction "2_2") (pintype "passive"))
      (node (ref "R16") (pin "2") (pinfunction "2_2") (pintype "passive"))
      (node (ref "R17") (pin "2") (pinfunction "2_2") (pintype "passive"))
      (node (ref "R19") (pin "2") (pinfunction "2_2") (pintype "passive"))
      (node (ref "R2") (pin "2") (pinfunction "2_2") (pintype "passive"))
      (node (ref "R20") (pin "2") (pinfunction "2_2") (pintype "passive"))
      (node (ref "R21") (pin "2") (pinfunction "2_2") (pintype "passive"))
      (node (ref "R23") (pin "2") (pinfunction "2_2") (pintype "passive"))
      (node (ref "R25") (pin "1") (pinfunction "1_1") (pintype "passive"))
      (node (ref "R3") (pin "2") (pinfunction "2_2") (pintype "passive"))
      (node (ref "R34") (pin "2") (pinfunction "2_2") (pintype "passive"))
      (node (ref "R38") (pin "1") (pinfunction "1_1") (pintype "passive"))
      (node (ref "R39") (pin "2") (pinfunction "2_2") (pintype "passive"))
      (node (ref "R40") (pin "2") (pinfunction "2_2") (pintype "passive"))
      (node (ref "R41") (pin "2") (pinfunction "2_2") (pintype "passive"))
      (node (ref "R7") (pin "1") (pinfunction "1_1") (pintype "passive"))
      (node (ref "U1") (pin "3") (pinfunction "GND_3") (pintype "passive"))
      (node (ref "U2") (pin "4") (pinfunction "GND_4") (pintype "passive"))
      (node (ref "U3") (pin "0") (pinfunction "PAD_0") (pintype "passive"))
      (node (ref "U3") (pin "11") (pinfunction "PEX_VSSD0_P0_11") (pintype "passive"))
      (node (ref "U3") (pin "16") (pinfunction "PEX_VSSA_P0_16") (pintype "passive"))
      (node (ref "U3") (pin "23") (pinfunction "MFG_AMC_23") (pintype "passive"))
      (node (ref "U3") (pin "26") (pinfunction "MFG_TAPEN_26") (pintype "passive"))
      (node (ref "U3") (pin "29") (pinfunction "VSS_29") (pintype "passive"))
      (node (ref "U3") (pin "3") (pinfunction "USB_AVSS_3") (pintype "passive"))
      (node (ref "U3") (pin "32") (pinfunction "VSS_32") (pintype "passive"))
      (node (ref "U3") (pin "4") (pinfunction "USB_PVSS_4") (pintype "passive"))
      (node (ref "U3") (pin "43") (pinfunction "PLL_AGND_43") (pintype "passive"))
      (node (ref "U3") (pin "58") (pinfunction "STRAP_PORTCFG_58") (pintype "passive"))
      (node (ref "U3") (pin "70") (pinfunction "PEX_VSSA_P2_70") (pintype "passive"))
      (node (ref "U3") (pin "74") (pinfunction "USB_VSSA_74") (pintype "passive"))
      (node (ref "U3") (pin "79") (pinfunction "USB_VSSD0_79") (pintype "passive"))
      (node (ref "U3") (pin "8") (pinfunction "PEX_VSSD1_P0_8") (pintype "passive"))
      (node (ref "U3") (pin "82") (pinfunction "USB_VSSD1_82") (pintype "passive"))
      (node (ref "U3") (pin "84") (pinfunction "MFG_TMC1_84") (pintype "passive"))
      (node (ref "U3") (pin "87") (pinfunction "MFG_TMC2_87") (pintype "passive"))
      (node (ref "U4") (pin "0") (pinfunction "PAD_0") (pintype "passive"))
      (node (ref "U4") (pin "19") (pinfunction "AGND1_19") (pintype "passive"))
      (node (ref "U4") (pin "2") (pinfunction "PGND1_2") (pintype "passive"))
      (node (ref "U4") (pin "5") (pinfunction "PGND2_5") (pintype "passive"))
      (node (ref "U4") (pin "8") (pinfunction "AGND2_8") (pintype "passive"))
      (node (ref "X1") (pin "0") (pinfunction "GND_0") (pintype "passive"))
      (node (ref "X1") (pin "5") (pinfunction "GND_5") (pintype "passive"))
      (node (ref "X1") (pin "8") (pinfunction "GND_8") (pintype "passive"))
      (node (ref "X10") (pin "2") (pinfunction "GND_2") (pintype "passive"))
      (node (ref "X11") (pin "2") (pinfunction "GND_2") (pintype "passive"))
      (node (ref "X12") (pin "2") (pinfunction "GND_2") (pintype "passive"))
      (node (ref "X13") (pin "2") (pinfunction "GND_2") (pintype "passive"))
      (node (ref "X14") (pin "2") (pinfunction "GND_2") (pintype "passive"))
      (node (ref "X15") (pin "2") (pinfunction "GND_2") (pintype "passive"))
      (node (ref "X16") (pin "2") (pinfunction "GND_2") (pintype "passive"))
      (node (ref "X17") (pin "2") (pinfunction "GND_2") (pintype "passive"))
      (node (ref "X18") (pin "2") (pinfunction "GND_2") (pintype "passive"))
      (node (ref "X3") (pin "2") (pinfunction "GND_2") (pintype "passive"))
      (node (ref "X5") (pin "0") (pinfunction "GND_0") (pintype "passive"))
      (node (ref "X5") (pin "15") (pinfunction "GND_15") (pintype "passive"))
      (node (ref "X5") (pin "18") (pinfunction "GND_18") (pintype "passive"))
      (node (ref "X5") (pin "21") (pinfunction "GND_21") (pintype "passive"))
      (node (ref "X5") (pin "26") (pinfunction "GND_26") (pintype "passive"))
      (node (ref "X5") (pin "27") (pinfunction "GND_27") (pintype "passive"))
      (node (ref "X5") (pin "29") (pinfunction "GND_29") (pintype "passive"))
      (node (ref "X5") (pin "34") (pinfunction "GND_34") (pintype "passive"))
      (node (ref "X5") (pin "35") (pinfunction "GND_35") (pintype "passive"))
      (node (ref "X5") (pin "37") (pinfunction "Reserved_37") (pintype "passive"))
      (node (ref "X5") (pin "4") (pinfunction "GND_4") (pintype "passive"))
      (node (ref "X5") (pin "40") (pinfunction "GND_40") (pintype "passive"))
      (node (ref "X5") (pin "43") (pinfunction "Reserved_43") (pintype "passive"))
      (node (ref "X5") (pin "50") (pinfunction "GND_50") (pintype "passive"))
      (node (ref "X5") (pin "9") (pinfunction "GND_9") (pintype "passive"))
      (node (ref "X6") (pin "0") (pinfunction "GND_0") (pintype "passive"))
      (node (ref "X6") (pin "5") (pinfunction "GND_5") (pintype "passive"))
      (node (ref "X7") (pin "2") (pinfunction "GND_2") (pintype "passive"))
      (node (ref "X8") (pin "6") (pinfunction "GND_6") (pintype "passive"))
      (node (ref "X9") (pin "2") (pinfunction "GND_2") (pintype "passive"))
    )
    (net (code "73") (name "Net-(L4-Pad1)") (class "Default")
      (node (ref "L4") (pin "1") (pinfunction "1_1") (pintype "passive"))
      (node (ref "R30") (pin "1") (pinfunction "1_1") (pintype "passive"))
    )
    (net (code "74") (name "Net-(L5-Pad1)") (class "Default")
      (node (ref "L5") (pin "1") (pinfunction "1_1") (pintype "passive"))
      (node (ref "R32") (pin "1") (pinfunction "1_1") (pintype "passive"))
    )
    (net (code "75") (name "Net-(LED1-K)") (class "Default")
      (node (ref "LED1") (pin "1") (pinfunction "K_1") (pintype "passive"))
      (node (ref "R41") (pin "1") (pinfunction "1_1") (pintype "passive"))
      (node (ref "R8") (pin "1") (pinfunction "1_1") (pintype "passive"))
    )
    (net (code "76") (name "Net-(LED2-K)") (class "Default")
      (node (ref "LED2") (pin "1") (pinfunction "K_1") (pintype "passive"))
      (node (ref "R40") (pin "1") (pinfunction "1_1") (pintype "passive"))
      (node (ref "R9") (pin "1") (pinfunction "1_1") (pintype "passive"))
    )
    (net (code "77") (name "Net-(LED3-K)") (class "Default")
      (node (ref "LED3") (pin "1") (pinfunction "K_1") (pintype "passive"))
      (node (ref "R10") (pin "1") (pinfunction "1_1") (pintype "passive"))
      (node (ref "R39") (pin "1") (pinfunction "1_1") (pintype "passive"))
    )
    (net (code "78") (name "Net-(U1-En)") (class "Default")
      (node (ref "C4") (pin "2") (pinfunction "2_2") (pintype "passive"))
      (node (ref "L1") (pin "1") (pinfunction "1_1") (pintype "passive"))
      (node (ref "U1") (pin "1") (pinfunction "En_1") (pintype "passive"))
      (node (ref "U1") (pin "6") (pinfunction "VCC_6") (pintype "passive"))
    )
    (net (code "79") (name "Net-(U4-EN1)") (class "Default")
      (node (ref "R35") (pin "1") (pinfunction "1_1") (pintype "passive"))
      (node (ref "U4") (pin "18") (pinfunction "EN1_18") (pintype "passive"))
    )
    (net (code "80") (name "Net-(U4-EN2)") (class "Default")
      (node (ref "R36") (pin "2") (pinfunction "2_2") (pintype "passive"))
      (node (ref "U4") (pin "9") (pinfunction "EN2_9") (pintype "passive"))
    )
    (net (code "81") (name "Net-(U4-FB1)") (class "Default")
      (node (ref "R33") (pin "1") (pinfunction "1_1") (pintype "passive"))
      (node (ref "R34") (pin "1") (pinfunction "1_1") (pintype "passive"))
      (node (ref "U4") (pin "16") (pinfunction "FB1_16") (pintype "passive"))
    )
    (net (code "82") (name "Net-(U4-FB2)") (class "Default")
      (node (ref "R37") (pin "2") (pinfunction "2_2") (pintype "passive"))
      (node (ref "R38") (pin "2") (pinfunction "2_2") (pintype "passive"))
      (node (ref "U4") (pin "11") (pinfunction "FB2_11") (pintype "passive"))
    )
    (net (code "83") (name "Net-(U4-SS1)") (class "Default")
      (node (ref "C20") (pin "2") (pinfunction "2_2") (pintype "passive"))
      (node (ref "U4") (pin "14") (pinfunction "SS1_14") (pintype "passive"))
    )
    (net (code "84") (name "Net-(U4-SS2)") (class "Default")
      (node (ref "C45") (pin "2") (pinfunction "2_2") (pintype "passive"))
      (node (ref "U4") (pin "13") (pinfunction "SS2_13") (pintype "passive"))
    )
    (net (code "85") (name "Net-(U4-SW1)") (class "Default")
      (node (ref "L3") (pin "2") (pinfunction "2_2") (pintype "passive"))
      (node (ref "U4") (pin "3") (pinfunction "SW1_3") (pintype "passive"))
    )
    (net (code "86") (name "Net-(U4-SW2)") (class "Default")
      (node (ref "L6") (pin "1") (pinfunction "1_1") (pintype "passive"))
      (node (ref "U4") (pin "4") (pinfunction "SW2_4") (pintype "passive"))
    )
    (net (code "87") (name "Net-(X10-Pad1)") (class "Default")
      (node (ref "X10") (pin "1") (pinfunction "1_1") (pintype "passive"))
      (node (ref "X15") (pin "1") (pinfunction "1_1") (pintype "passive"))
    )
    (net (code "88") (name "Net-(X11-Pad1)") (class "Default")
      (node (ref "X11") (pin "1") (pinfunction "1_1") (pintype "passive"))
      (node (ref "X16") (pin "1") (pinfunction "1_1") (pintype "passive"))
    )
    (net (code "89") (name "Net-(X12-Pad1)") (class "Default")
      (node (ref "X12") (pin "1") (pinfunction "1_1") (pintype "passive"))
      (node (ref "X17") (pin "1") (pinfunction "1_1") (pintype "passive"))
    )
    (net (code "90") (name "Net-(X13-Pad1)") (class "Default")
      (node (ref "X13") (pin "1") (pinfunction "1_1") (pintype "passive"))
      (node (ref "X18") (pin "1") (pinfunction "1_1") (pintype "passive"))
    )
    (net (code "91") (name "Net-(X14-Pad1)") (class "Default")
      (node (ref "X14") (pin "1") (pinfunction "1_1") (pintype "passive"))
      (node (ref "X9") (pin "1") (pinfunction "1_1") (pintype "passive"))
    )
    (net (code "92") (name "VAUX+1.0V") (class "Default")
      (node (ref "C17") (pin "1") (pinfunction "1_1") (pintype "passive"))
      (node (ref "C21") (pin "1") (pinfunction "1_1") (pintype "passive"))
      (node (ref "C26") (pin "2") (pinfunction "2_2") (pintype "passive"))
      (node (ref "C34") (pin "2") (pinfunction "2_2") (pintype "passive"))
      (node (ref "R28") (pin "1") (pinfunction "1_1") (pintype "passive"))
      (node (ref "U3") (pin "18") (pinfunction "VAUX_CORE_18") (pintype "passive"))
      (node (ref "U3") (pin "72") (pinfunction "VAUX_CORE_72") (pintype "passive"))
    )
    (net (code "93") (name "VCC+5V") (class "Default")
      (node (ref "C13") (pin "2") (pinfunction "2_2") (pintype "passive"))
      (node (ref "C15") (pin "2") (pinfunction "2_2") (pintype "passive"))
      (node (ref "C41") (pin "2") (pinfunction "2_2") (pintype "passive"))
      (node (ref "C47") (pin "2") (pinfunction "2_2") (pintype "passive"))
      (node (ref "L2") (pin "2") (pinfunction "2_2") (pintype "passive"))
      (node (ref "R35") (pin "2") (pinfunction "2_2") (pintype "passive"))
      (node (ref "R36") (pin "1") (pinfunction "1_1") (pintype "passive"))
      (node (ref "R6") (pin "2") (pinfunction "2_2") (pintype "passive"))
      (node (ref "U4") (pin "1") (pinfunction "VIN1_1") (pintype "passive"))
      (node (ref "U4") (pin "20") (pinfunction "AVIN1_20") (pintype "passive"))
      (node (ref "U4") (pin "6") (pinfunction "VIN2_6") (pintype "passive"))
      (node (ref "U4") (pin "7") (pinfunction "AVIN2_7") (pintype "passive"))
    )
    (net (code "94") (name "unconnected-(CJ1-Pad)") (class "Default")
      (node (ref "CJ1") (pin "") (pintype "passive"))
    )
    (net (code "95") (name "unconnected-(CJ2-Pad)") (class "Default")
      (node (ref "CJ2") (pin "") (pintype "passive"))
    )
    (net (code "96") (name "unconnected-(CJ3-Pad)") (class "Default")
      (node (ref "CJ3") (pin "") (pintype "passive"))
    )
    (net (code "97") (name "unconnected-(CJ4-Pad)") (class "Default")
      (node (ref "CJ4") (pin "") (pintype "passive"))
    )
    (net (code "98") (name "unconnected-(CJ5-Pad)") (class "Default")
      (node (ref "CJ5") (pin "") (pintype "passive"))
    )
    (net (code "99") (name "unconnected-(E1-Pad)") (class "Default")
      (node (ref "E1") (pin "") (pintype "passive"))
    )
    (net (code "100") (name "unconnected-(E2-Pad)") (class "Default")
      (node (ref "E2") (pin "") (pintype "passive"))
    )
    (net (code "101") (name "unconnected-(E3-Pad)") (class "Default")
      (node (ref "E3") (pin "") (pintype "passive"))
    )
    (net (code "102") (name "unconnected-(E4-Pad)") (class "Default")
      (node (ref "E4") (pin "") (pintype "passive"))
    )
    (net (code "103") (name "unconnected-(E5-Pad)") (class "Default")
      (node (ref "E5") (pin "") (pintype "passive"))
    )
    (net (code "104") (name "unconnected-(E6-Pad)") (class "Default")
      (node (ref "E6") (pin "") (pintype "passive"))
    )
    (net (code "105") (name "unconnected-(E7-Pad)") (class "Default")
      (node (ref "E7") (pin "") (pintype "passive"))
    )
    (net (code "106") (name "unconnected-(LOGO1-Pad1)") (class "Default")
      (node (ref "LOGO1") (pin "1") (pinfunction "1_1") (pintype "passive"))
    )
    (net (code "107") (name "unconnected-(TG1-Pad)") (class "Default")
      (node (ref "TG1") (pin "") (pintype "passive"))
    )
    (net (code "108") (name "unconnected-(U1-NC-Pad2)") (class "Default")
      (node (ref "U1") (pin "2") (pinfunction "NC_2") (pintype "passive+no_connect"))
    )
    (net (code "109") (name "unconnected-(U3-PROCMON-Pad68)") (class "Default")
      (node (ref "U3") (pin "68") (pinfunction "PROCMON_68") (pintype "passive+no_connect"))
    )
    (net (code "110") (name "unconnected-(U3-STRAP_TESTMODE2-Pad46)") (class "Default")
      (node (ref "U3") (pin "46") (pinfunction "STRAP_TESTMODE2_46") (pintype "passive+no_connect"))
    )
    (net (code "111") (name "unconnected-(U3-STRAP_TESTMODE3-Pad47)") (class "Default")
      (node (ref "U3") (pin "47") (pinfunction "STRAP_TESTMODE3_47") (pintype "passive+no_connect"))
    )
    (net (code "112") (name "unconnected-(U3-~{STRAP_PLL_BYPASS}-Pad65)") (class "Default")
      (node (ref "U3") (pin "65") (pinfunction "~{STRAP_PLL_BYPASS}_65") (pintype "passive+no_connect"))
    )
    (net (code "113") (name "unconnected-(U3-~{STRAP_PROBE_MODE}-Pad19)") (class "Default")
      (node (ref "U3") (pin "19") (pinfunction "~{STRAP_PROBE_MODE}_19") (pintype "passive+no_connect"))
    )
    (net (code "114") (name "unconnected-(U3-~{STRAP_SERDES_MODE_EN}-Pad56)") (class "Default")
      (node (ref "U3") (pin "56") (pinfunction "~{STRAP_SERDES_MODE_EN}_56") (pintype "passive+no_connect"))
    )
    (net (code "115") (name "unconnected-(U4-PG1-Pad15)") (class "Default")
      (node (ref "U4") (pin "15") (pinfunction "PG1_15") (pintype "passive+no_connect"))
    )
    (net (code "116") (name "unconnected-(U4-PG2-Pad12)") (class "Default")
      (node (ref "U4") (pin "12") (pinfunction "PG2_12") (pintype "passive+no_connect"))
    )
    (net (code "117") (name "unconnected-(X1-ID-Pad4)") (class "Default")
      (node (ref "X1") (pin "4") (pinfunction "ID_4") (pintype "passive+no_connect"))
    )
    (net (code "118") (name "unconnected-(X5-+1.5V-Pad6)") (class "Default")
      (node (ref "X5") (pin "6") (pinfunction "+1.5V_6") (pintype "passive+no_connect"))
    )
    (net (code "119") (name "unconnected-(X5-+1.5V-Pad28)") (class "Default")
      (node (ref "X5") (pin "28") (pinfunction "+1.5V_28") (pintype "passive+no_connect"))
    )
    (net (code "120") (name "unconnected-(X5-+1.5V-Pad48)") (class "Default")
      (node (ref "X5") (pin "48") (pinfunction "+1.5V_48") (pintype "passive+no_connect"))
    )
    (net (code "121") (name "unconnected-(X5-+3.3Vaux-Pad24)") (class "Default")
      (node (ref "X5") (pin "24") (pinfunction "+3.3Vaux_24") (pintype "passive+no_connect"))
    )
    (net (code "122") (name "unconnected-(X5-CLKREQ#-Pad7)") (class "Default")
      (node (ref "X5") (pin "7") (pinfunction "CLKREQ#_7") (pintype "passive+no_connect"))
    )
    (net (code "123") (name "unconnected-(X5-Reserved-Pad39)") (class "Default")
      (node (ref "X5") (pin "39") (pinfunction "Reserved_39") (pintype "passive+no_connect"))
    )
    (net (code "124") (name "unconnected-(X5-Reserved-Pad41)") (class "Default")
      (node (ref "X5") (pin "41") (pinfunction "Reserved_41") (pintype "passive+no_connect"))
    )
    (net (code "125") (name "unconnected-(X5-Reserved-Pad45)") (class "Default")
      (node (ref "X5") (pin "45") (pinfunction "Reserved_45") (pintype "passive+no_connect"))
    )
    (net (code "126") (name "unconnected-(X5-Reserved-Pad47)") (class "Default")
      (node (ref "X5") (pin "47") (pinfunction "Reserved_47") (pintype "passive+no_connect"))
    )
    (net (code "127") (name "unconnected-(X5-Reserved-Pad49)") (class "Default")
      (node (ref "X5") (pin "49") (pinfunction "Reserved_49") (pintype "passive+no_connect"))
    )
    (net (code "128") (name "unconnected-(X5-Reserved-Pad51)") (class "Default")
      (node (ref "X5") (pin "51") (pinfunction "Reserved_51") (pintype "passive+no_connect"))
    )
    (net (code "129") (name "unconnected-(X5-UIM_VPP-Pad16)") (class "Default")
      (node (ref "X5") (pin "16") (pinfunction "UIM_VPP_16") (pintype "passive+no_connect"))
    )
    (net (code "130") (name "unconnected-(X5-USB_DM-Pad36)") (class "Default")
      (node (ref "X5") (pin "36") (pinfunction "USB_DM_36") (pintype "passive+no_connect"))
    )
    (net (code "131") (name "unconnected-(X5-USB_DP-Pad38)") (class "Default")
      (node (ref "X5") (pin "38") (pinfunction "USB_DP_38") (pintype "passive+no_connect"))
    )
    (net (code "132") (name "unconnected-(X6-PRES-Pad8)") (class "Default")
      (node (ref "X6") (pin "8") (pinfunction "PRES_8") (pintype "passive+no_connect"))
    )
    (net (code "133") (name "unconnected-(X6-VPP-Pad6)") (class "Default")
      (node (ref "X6") (pin "6") (pinfunction "VPP_6") (pintype "passive+no_connect"))
    )
    (net (code "134") (name "unconnected-(X8A-VIO-Pad4)") (class "Default")
      (node (ref "X8") (pin "4") (pinfunction "VIO_4") (pintype "passive+no_connect"))
    )
  )
)
